# M865C.net
KiCad netlist of a schematic drawn in EAGLE
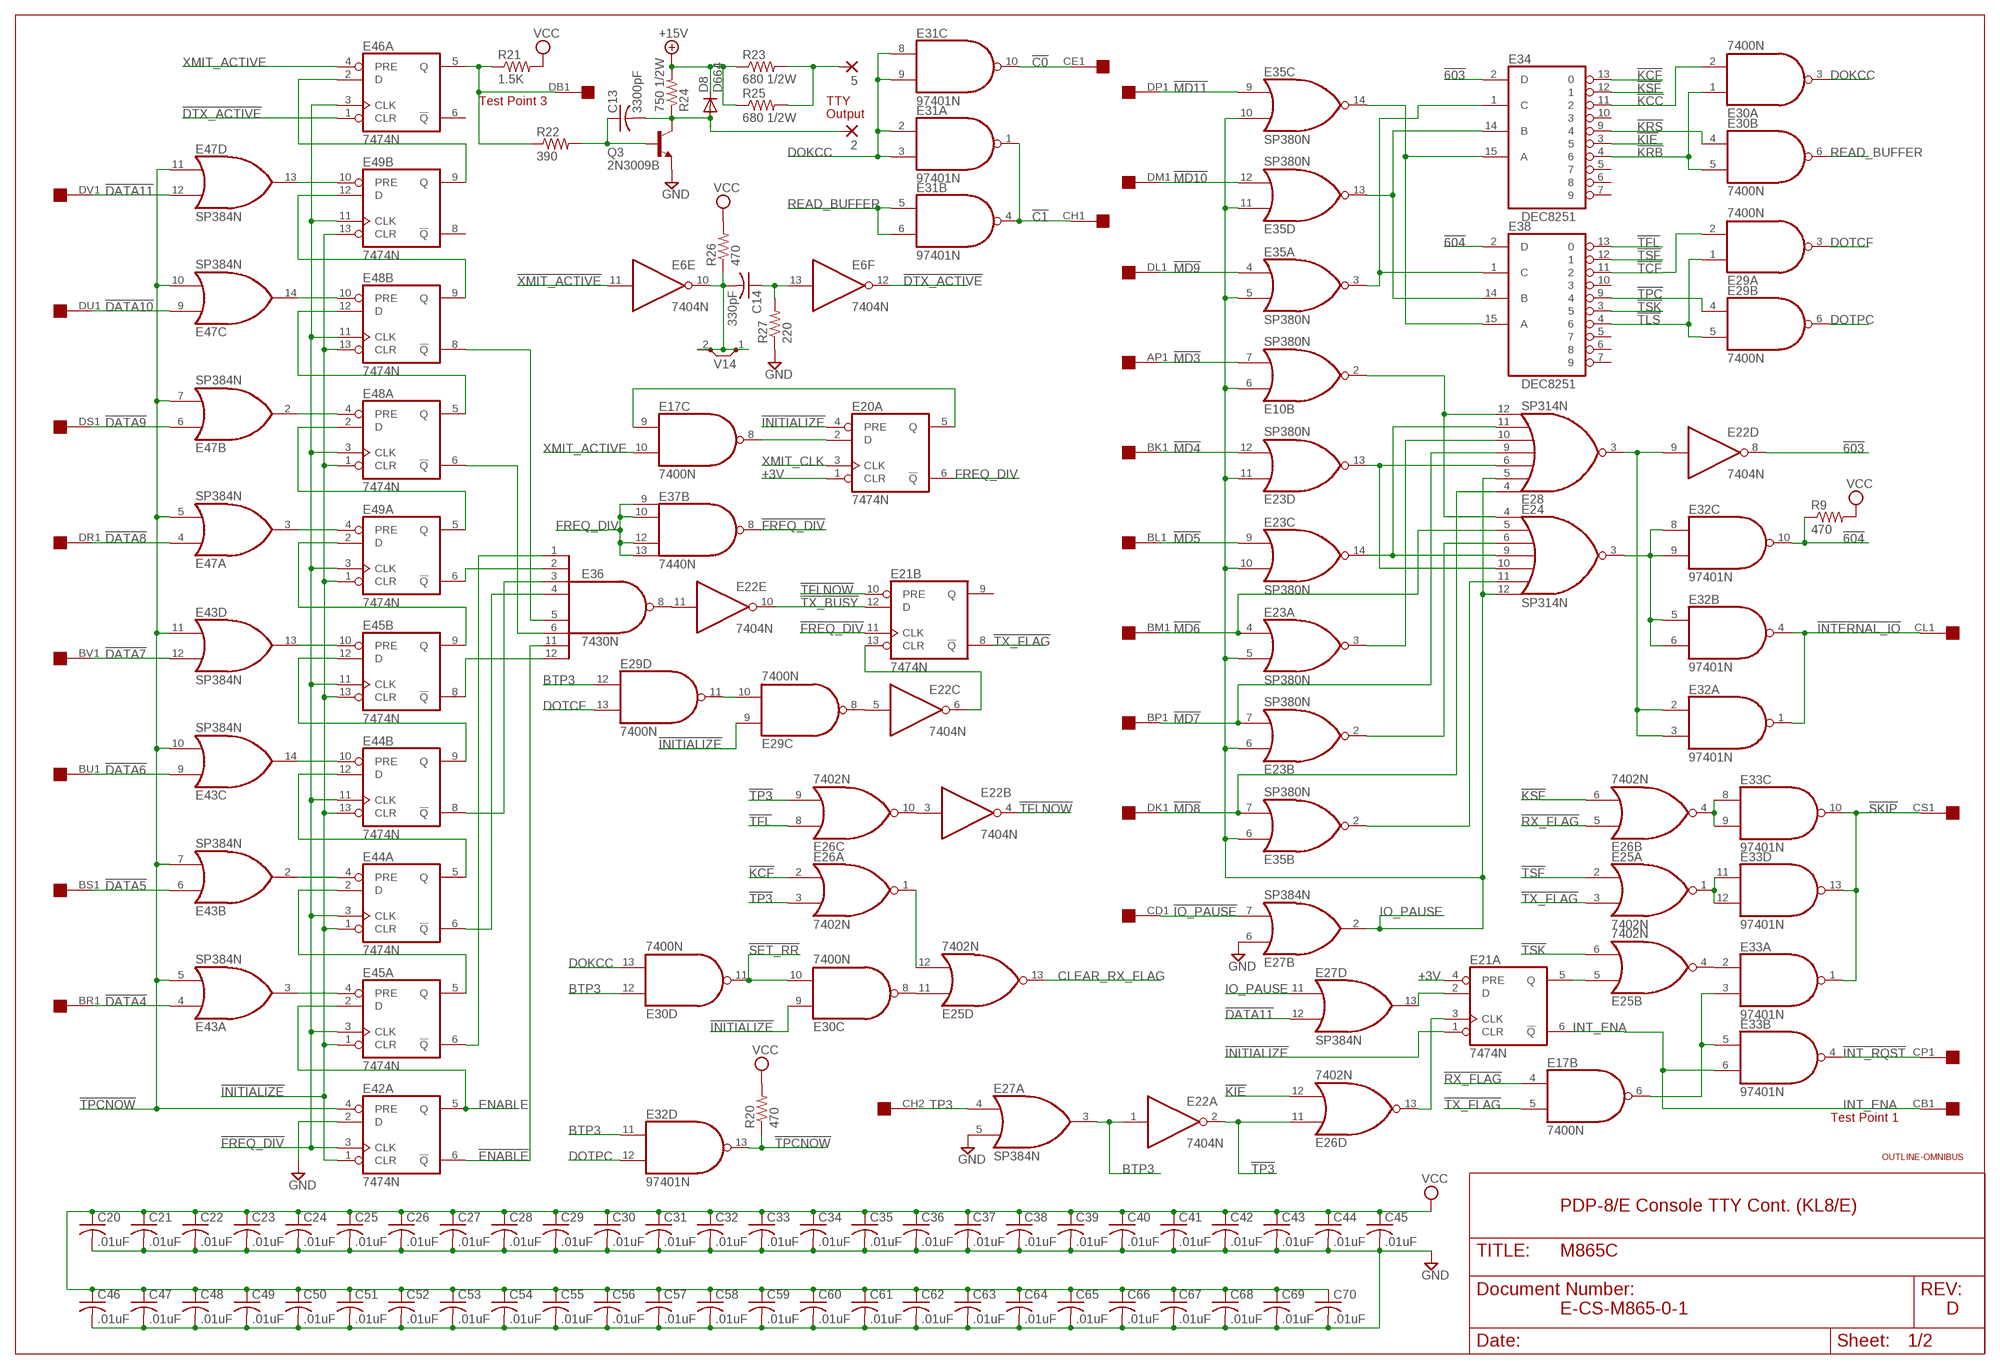
[diagram p0: schematic, sheet 1]
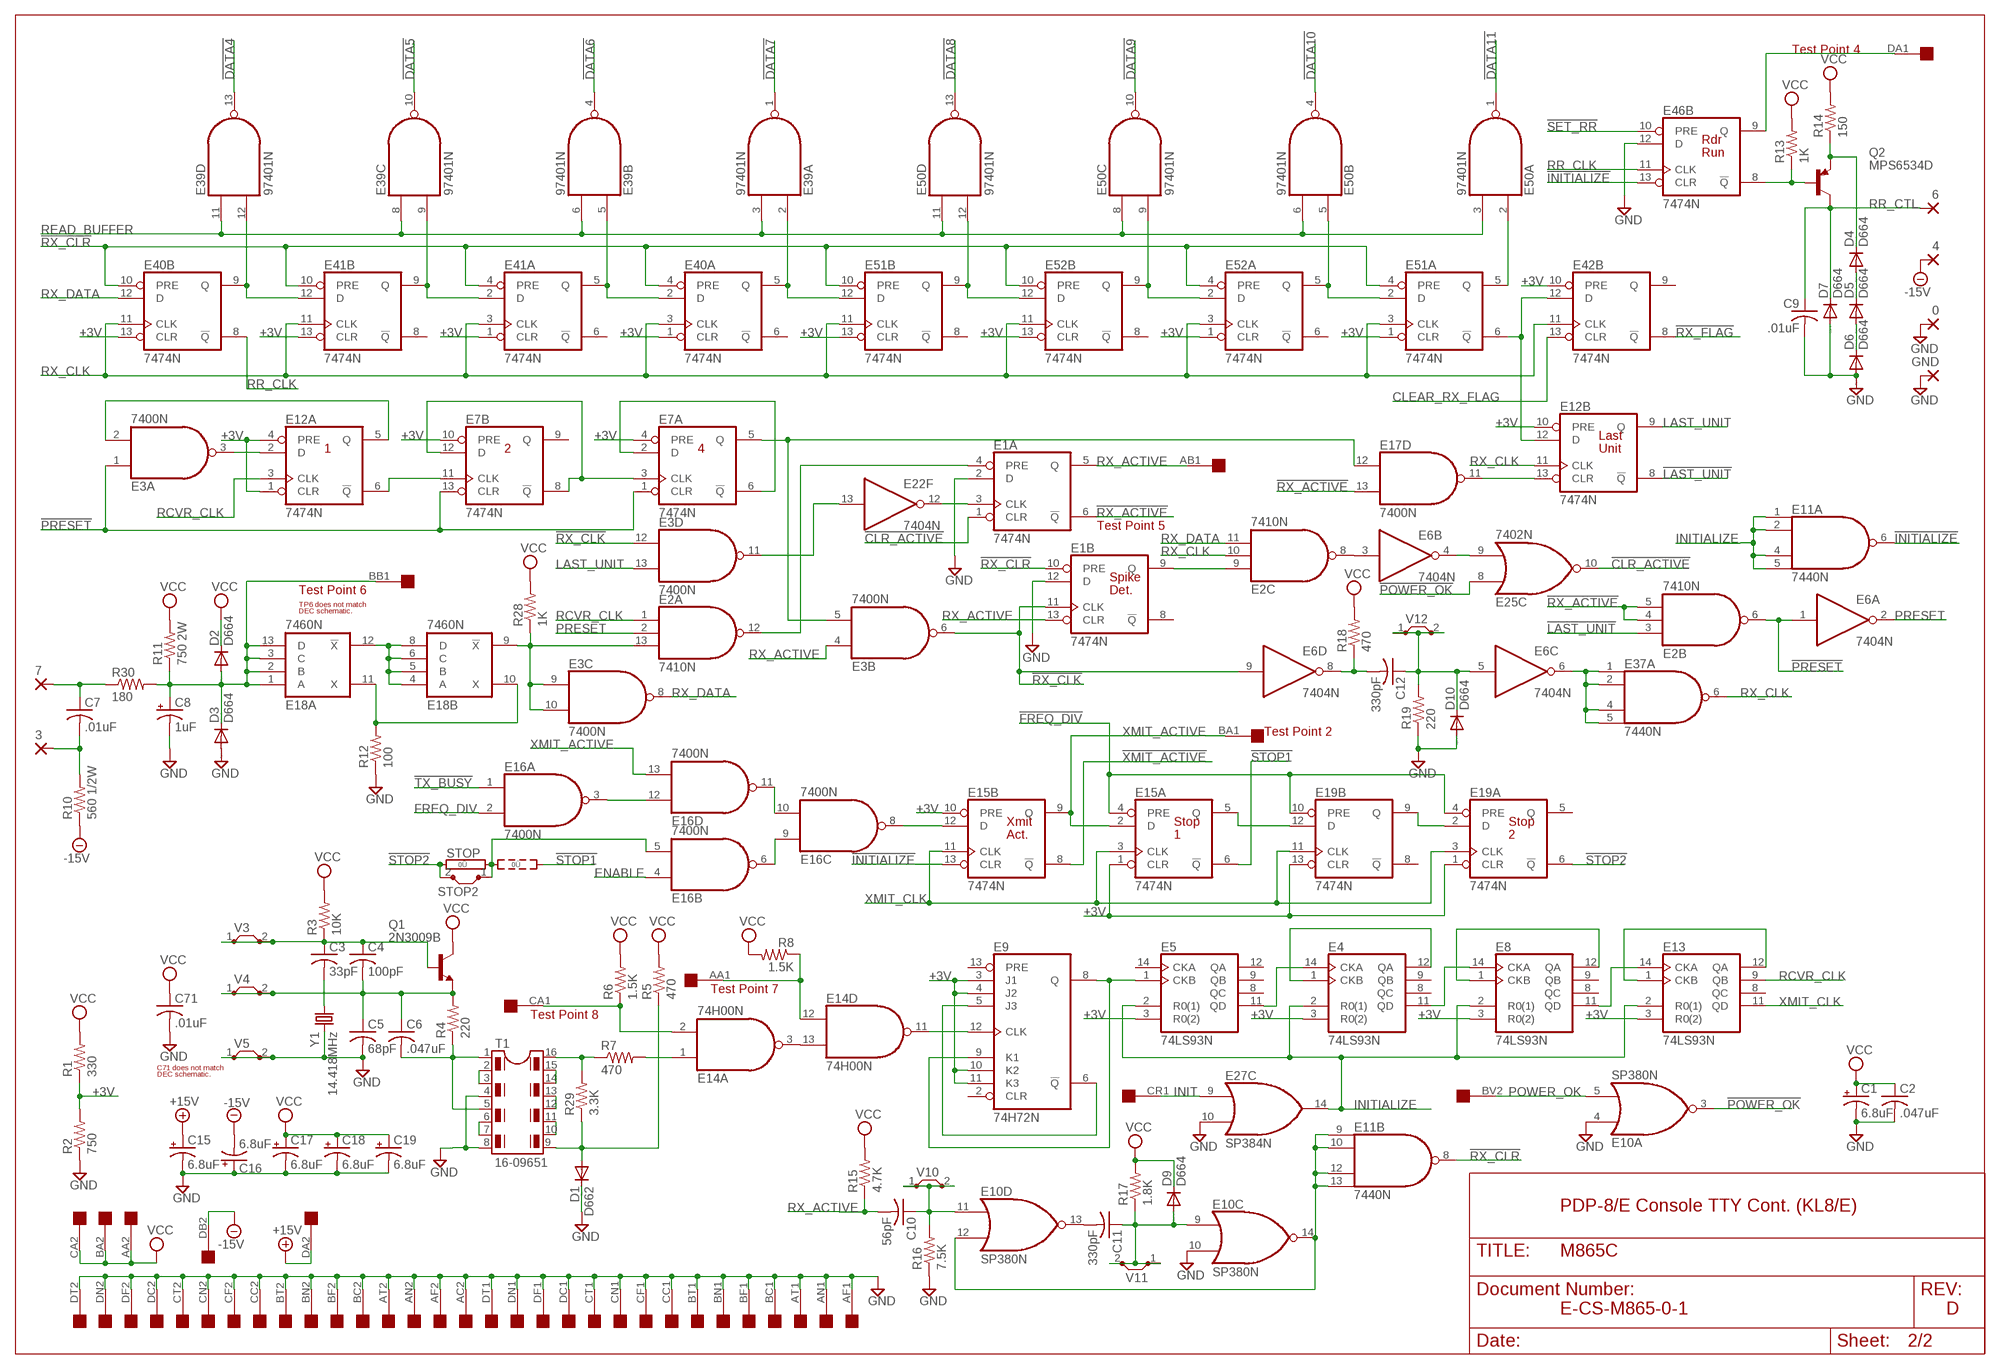
[diagram p1: schematic, sheet 2]

(export (version "E")
  (design (tool "Eeschema 10.0.6"))
  (components
    (comp (ref "0")
      (value "2,15/1,0")
      (footprint "eagle-import:2,15_1,0")
      (libsource (lib "eagle-import") (part "2,15/1,0"))
    )
    (comp (ref "3")
      (value "2,15/1,0")
      (footprint "eagle-import:2,15_1,0")
      (libsource (lib "eagle-import") (part "2,15/1,0"))
    )
    (comp (ref "4")
      (value "2,15/1,0")
      (footprint "eagle-import:2,15_1,0")
      (libsource (lib "eagle-import") (part "2,15/1,0"))
    )
    (comp (ref "6")
      (value "2,15/1,0")
      (footprint "eagle-import:2,15_1,0")
      (libsource (lib "eagle-import") (part "2,15/1,0"))
    )
    (comp (ref "7")
      (value "2,15/1,0")
      (footprint "eagle-import:2,15_1,0")
      (libsource (lib "eagle-import") (part "2,15/1,0"))
    )
    (comp (ref "C1")
      (value "6.8uF")
      (footprint "eagle-import:E12-8")
      (libsource (lib "eagle-import") (part "CPOL-USE20-8AXIAL"))
    )
    (comp (ref "C2")
      (value ".047uF")
      (footprint "eagle-import:C075-032X103")
      (libsource (lib "eagle-import") (part "C-US075-032X103"))
    )
    (comp (ref "C3")
      (value "33pF")
      (footprint "eagle-import:C050-025X075")
      (libsource (lib "eagle-import") (part "C-US050-025X075"))
    )
    (comp (ref "C4")
      (value "100pF")
      (footprint "eagle-import:C050-025X075")
      (libsource (lib "eagle-import") (part "C-US050-025X075"))
    )
    (comp (ref "C5")
      (value "68pF")
      (footprint "eagle-import:C050-025X075")
      (libsource (lib "eagle-import") (part "C-US050-025X075"))
    )
    (comp (ref "C6")
      (value ".047uF")
      (footprint "eagle-import:C075-032X103")
      (libsource (lib "eagle-import") (part "C-US075-032X103"))
    )
    (comp (ref "C7")
      (value ".01uF")
      (footprint "eagle-import:C050-025X075")
      (libsource (lib "eagle-import") (part "C-US050-025X075"))
    )
    (comp (ref "C8")
      (value "1uF")
      (footprint "eagle-import:E15-5")
      (libsource (lib "eagle-import") (part "CPOL-USE15-5AXIAL"))
    )
    (comp (ref "C9")
      (value ".01uF")
      (footprint "eagle-import:C050-025X075")
      (libsource (lib "eagle-import") (part "C-US050-025X075"))
    )
    (comp (ref "C10")
      (value "56pF")
      (footprint "eagle-import:C050-025X075")
      (libsource (lib "eagle-import") (part "C-US050-025X075"))
    )
    (comp (ref "C11")
      (value "330pF")
      (footprint "eagle-import:C050-025X075")
      (libsource (lib "eagle-import") (part "C-US050-025X075"))
    )
    (comp (ref "C12")
      (value "330pF")
      (footprint "eagle-import:C050-025X075")
      (libsource (lib "eagle-import") (part "C-US050-025X075"))
    )
    (comp (ref "C15")
      (value "6.8uF")
      (footprint "eagle-import:E12-8")
      (libsource (lib "eagle-import") (part "CPOL-USE20-8AXIAL"))
    )
    (comp (ref "C16")
      (value "6.8uF")
      (footprint "eagle-import:E12-8")
      (libsource (lib "eagle-import") (part "CPOL-USE20-8AXIAL"))
    )
    (comp (ref "C17")
      (value "6.8uF")
      (footprint "eagle-import:E12-8")
      (libsource (lib "eagle-import") (part "CPOL-USE20-8AXIAL"))
    )
    (comp (ref "C18")
      (value "6.8uF")
      (footprint "eagle-import:E12-8")
      (libsource (lib "eagle-import") (part "CPOL-USE20-8AXIAL"))
    )
    (comp (ref "C19")
      (value "6.8uF")
      (footprint "eagle-import:E12-8")
      (libsource (lib "eagle-import") (part "CPOL-USE20-8AXIAL"))
    )
    (comp (ref "C71")
      (value ".01uF")
      (footprint "eagle-import:C050-025X075")
      (libsource (lib "eagle-import") (part "C-US050-025X075"))
    )
    (comp (ref "D1")
      (value "D662")
      (footprint "eagle-import:DO35-10")
      (libsource (lib "eagle-import") (part "DIODE-DO35-10"))
    )
    (comp (ref "D2")
      (value "D664")
      (footprint "eagle-import:DO35-10")
      (libsource (lib "eagle-import") (part "DIODE-DO35-10"))
    )
    (comp (ref "D3")
      (value "D664")
      (footprint "eagle-import:DO35-10")
      (libsource (lib "eagle-import") (part "DIODE-DO35-10"))
    )
    (comp (ref "D4")
      (value "D664")
      (footprint "eagle-import:DO35-10")
      (libsource (lib "eagle-import") (part "DIODE-DO35-10"))
    )
    (comp (ref "D5")
      (value "D664")
      (footprint "eagle-import:DO35-10")
      (libsource (lib "eagle-import") (part "DIODE-DO35-10"))
    )
    (comp (ref "D6")
      (value "D664")
      (footprint "eagle-import:DO35-10")
      (libsource (lib "eagle-import") (part "DIODE-DO35-10"))
    )
    (comp (ref "D7")
      (value "D664")
      (footprint "eagle-import:DO35-10")
      (libsource (lib "eagle-import") (part "DIODE-DO35-10"))
    )
    (comp (ref "D9")
      (value "D664")
      (footprint "eagle-import:DO35-10")
      (libsource (lib "eagle-import") (part "DIODE-DO35-10"))
    )
    (comp (ref "D10")
      (value "D664")
      (footprint "eagle-import:DO35-10")
      (libsource (lib "eagle-import") (part "DIODE-DO35-10"))
    )
    (comp (ref "E1")
      (value "7474N")
      (footprint "eagle-import:DIL14")
      (libsource (lib "eagle-import") (part "7474NS"))
    )
    (comp (ref "E2")
      (value "7410N")
      (footprint "eagle-import:DIL14")
      (libsource (lib "eagle-import") (part "7410N"))
    )
    (comp (ref "E3")
      (value "7400N")
      (footprint "eagle-import:DIL14")
      (libsource (lib "eagle-import") (part "7400N"))
    )
    (comp (ref "E4")
      (value "74LS93N")
      (footprint "eagle-import:DIL14")
      (libsource (lib "eagle-import") (part "7493NLS"))
    )
    (comp (ref "E5")
      (value "74LS93N")
      (footprint "eagle-import:DIL14")
      (libsource (lib "eagle-import") (part "7493NLS"))
    )
    (comp (ref "E6")
      (value "7404N")
      (footprint "eagle-import:DIL14")
      (libsource (lib "eagle-import") (part "7404N"))
    )
    (comp (ref "E7")
      (value "7474N")
      (footprint "eagle-import:DIL14")
      (libsource (lib "eagle-import") (part "7474NS"))
    )
    (comp (ref "E8")
      (value "74LS93N")
      (footprint "eagle-import:DIL14")
      (libsource (lib "eagle-import") (part "7493NLS"))
    )
    (comp (ref "E9")
      (value "74H72N")
      (footprint "eagle-import:DIL14")
      (libsource (lib "eagle-import") (part "7472N"))
    )
    (comp (ref "E10")
      (value "SP380N")
      (footprint "eagle-import:DIL14")
      (libsource (lib "eagle-import") (part "SP380N"))
    )
    (comp (ref "E11")
      (value "7440N")
      (footprint "eagle-import:DIL14")
      (libsource (lib "eagle-import") (part "7440N"))
    )
    (comp (ref "E12")
      (value "7474N")
      (footprint "eagle-import:DIL14")
      (libsource (lib "eagle-import") (part "7474NS"))
    )
    (comp (ref "E13")
      (value "74LS93N")
      (footprint "eagle-import:DIL14")
      (libsource (lib "eagle-import") (part "7493NLS"))
    )
    (comp (ref "E14")
      (value "74H00N")
      (footprint "eagle-import:DIL14")
      (libsource (lib "eagle-import") (part "7400N"))
    )
    (comp (ref "E15")
      (value "7474N")
      (footprint "eagle-import:DIL14")
      (libsource (lib "eagle-import") (part "7474NS"))
    )
    (comp (ref "E16")
      (value "7400N")
      (footprint "eagle-import:DIL14")
      (libsource (lib "eagle-import") (part "7400N"))
    )
    (comp (ref "E17")
      (value "7400N")
      (footprint "eagle-import:DIL14")
      (libsource (lib "eagle-import") (part "7400N"))
    )
    (comp (ref "E18")
      (value "7460N")
      (footprint "eagle-import:DIL14")
      (libsource (lib "eagle-import") (part "7460N"))
    )
    (comp (ref "E19")
      (value "7474N")
      (footprint "eagle-import:DIL14")
      (libsource (lib "eagle-import") (part "7474NS"))
    )
    (comp (ref "E22")
      (value "7404N")
      (footprint "eagle-import:DIL14")
      (libsource (lib "eagle-import") (part "7404N"))
    )
    (comp (ref "E25")
      (value "7402N")
      (footprint "eagle-import:DIL14")
      (libsource (lib "eagle-import") (part "7402N"))
    )
    (comp (ref "E27")
      (value "SP384N")
      (footprint "eagle-import:DIL14")
      (libsource (lib "eagle-import") (part "SP384N"))
    )
    (comp (ref "E37")
      (value "7440N")
      (footprint "eagle-import:DIL14")
      (libsource (lib "eagle-import") (part "7440N"))
    )
    (comp (ref "E39")
      (value "97401N")
      (footprint "eagle-import:DIL14")
      (libsource (lib "eagle-import") (part "7401NLS"))
    )
    (comp (ref "E40")
      (value "7474N")
      (footprint "eagle-import:DIL14")
      (libsource (lib "eagle-import") (part "7474NS"))
    )
    (comp (ref "E41")
      (value "7474N")
      (footprint "eagle-import:DIL14")
      (libsource (lib "eagle-import") (part "7474NS"))
    )
    (comp (ref "E42")
      (value "7474N")
      (footprint "eagle-import:DIL14")
      (libsource (lib "eagle-import") (part "7474NS"))
    )
    (comp (ref "E46")
      (value "7474N")
      (footprint "eagle-import:DIL14")
      (libsource (lib "eagle-import") (part "7474NS"))
    )
    (comp (ref "E50")
      (value "97401N")
      (footprint "eagle-import:DIL14")
      (libsource (lib "eagle-import") (part "7401NLS"))
    )
    (comp (ref "E51")
      (value "7474N")
      (footprint "eagle-import:DIL14")
      (libsource (lib "eagle-import") (part "7474NS"))
    )
    (comp (ref "E52")
      (value "7474N")
      (footprint "eagle-import:DIL14")
      (libsource (lib "eagle-import") (part "7474NS"))
    )
    (comp (ref "GND")
      (value "2,15/1,0")
      (footprint "eagle-import:2,15_1,0")
      (libsource (lib "eagle-import") (part "2,15/1,0"))
    )
    (comp (ref "Q1")
      (value "2N3009B")
      (footprint "eagle-import:TO5")
      (libsource (lib "eagle-import") (part "-NPN-TO5"))
    )
    (comp (ref "Q2")
      (value "MPS6534D")
      (footprint "eagle-import:TO5")
      (libsource (lib "eagle-import") (part "-PNP-TO5"))
    )
    (comp (ref "R1")
      (value "330")
      (footprint "eagle-import:0207_10")
      (libsource (lib "eagle-import") (part "R-US_0207/10"))
    )
    (comp (ref "R2")
      (value "750")
      (footprint "eagle-import:0207_10")
      (libsource (lib "eagle-import") (part "R-US_0207/10"))
    )
    (comp (ref "R3")
      (value "10K")
      (footprint "eagle-import:0207_10")
      (libsource (lib "eagle-import") (part "R-US_0207/10"))
    )
    (comp (ref "R4")
      (value "220")
      (footprint "eagle-import:0207_10")
      (libsource (lib "eagle-import") (part "R-US_0207/10"))
    )
    (comp (ref "R5")
      (value "470")
      (footprint "eagle-import:0207_10")
      (libsource (lib "eagle-import") (part "R-US_0207/10"))
    )
    (comp (ref "R6")
      (value "1.5K")
      (footprint "eagle-import:0207_10")
      (libsource (lib "eagle-import") (part "R-US_0207/10"))
    )
    (comp (ref "R7")
      (value "470")
      (footprint "eagle-import:0207_10")
      (libsource (lib "eagle-import") (part "R-US_0207/10"))
    )
    (comp (ref "R8")
      (value "1.5K")
      (footprint "eagle-import:0207_10")
      (libsource (lib "eagle-import") (part "R-US_0207/10"))
    )
    (comp (ref "R10")
      (value "560 1/2W")
      (footprint "eagle-import:0411_15")
      (libsource (lib "eagle-import") (part "R-US_0411/15"))
    )
    (comp (ref "R11")
      (value "750 2W")
      (footprint "eagle-import:0818_25")
      (libsource (lib "eagle-import") (part "R-US_0818/25"))
    )
    (comp (ref "R12")
      (value "100")
      (footprint "eagle-import:0207_10")
      (libsource (lib "eagle-import") (part "R-US_0207/10"))
    )
    (comp (ref "R13")
      (value "1K")
      (footprint "eagle-import:0207_10")
      (libsource (lib "eagle-import") (part "R-US_0207/10"))
    )
    (comp (ref "R14")
      (value "150")
      (footprint "eagle-import:0207_10")
      (libsource (lib "eagle-import") (part "R-US_0207/10"))
    )
    (comp (ref "R15")
      (value "4.7K")
      (footprint "eagle-import:0207_10")
      (libsource (lib "eagle-import") (part "R-US_0207/10"))
    )
    (comp (ref "R16")
      (value "7.5K")
      (footprint "eagle-import:0207_10")
      (libsource (lib "eagle-import") (part "R-US_0207/10"))
    )
    (comp (ref "R17")
      (value "1.8K")
      (footprint "eagle-import:0207_10")
      (libsource (lib "eagle-import") (part "R-US_0207/10"))
    )
    (comp (ref "R18")
      (value "470")
      (footprint "eagle-import:0207_10")
      (libsource (lib "eagle-import") (part "R-US_0207/10"))
    )
    (comp (ref "R19")
      (value "220")
      (footprint "eagle-import:0207_10")
      (libsource (lib "eagle-import") (part "R-US_0207/10"))
    )
    (comp (ref "R28")
      (value "1K")
      (footprint "eagle-import:0207_10")
      (libsource (lib "eagle-import") (part "R-US_0207/10"))
    )
    (comp (ref "R29")
      (value "3.3K")
      (footprint "eagle-import:0207_10")
      (libsource (lib "eagle-import") (part "R-US_0207/10"))
    )
    (comp (ref "R30")
      (value "180")
      (footprint "eagle-import:0207_10")
      (libsource (lib "eagle-import") (part "R-US_0207/10"))
    )
    (comp (ref "STOP")
      (value "0R2")
      (footprint "eagle-import:0R2_10")
      (libsource (lib "eagle-import") (part "0R2"))
    )
    (comp (ref "STOP2")
      (value "J10MM")
      (footprint "eagle-import:10")
      (libsource (lib "eagle-import") (part "J10MM"))
    )
    (comp (ref "T1")
      (value "16-09651")
      (footprint "eagle-import:DIL16")
      (libsource (lib "eagle-import") (part "DIL16"))
    )
    (comp (ref "U$1")
      (value "QUAD")
      (footprint "eagle-import:EDGE-CON8")
      (libsource (lib "eagle-import") (part "QUAD"))
    )
    (comp (ref "V3")
      (value "J10MM")
      (footprint "eagle-import:10")
      (libsource (lib "eagle-import") (part "J10MM"))
    )
    (comp (ref "V4")
      (value "J10MM")
      (footprint "eagle-import:10")
      (libsource (lib "eagle-import") (part "J10MM"))
    )
    (comp (ref "V5")
      (value "J10MM")
      (footprint "eagle-import:10")
      (libsource (lib "eagle-import") (part "J10MM"))
    )
    (comp (ref "V10")
      (value "J10MM")
      (footprint "eagle-import:10")
      (libsource (lib "eagle-import") (part "J10MM"))
    )
    (comp (ref "V11")
      (value "J10MM")
      (footprint "eagle-import:10")
      (libsource (lib "eagle-import") (part "J10MM"))
    )
    (comp (ref "V12")
      (value "J10MM")
      (footprint "eagle-import:10")
      (libsource (lib "eagle-import") (part "J10MM"))
    )
    (comp (ref "Y1")
      (value "14.418MHz")
      (footprint "eagle-import:HC18U-H")
      (libsource (lib "eagle-import") (part "CRYSTALHC18U-H"))
    )
    (comp (ref "2")
      (value "2,15/1,0")
      (footprint "eagle-import:2,15_1,0")
      (libsource (lib "eagle-import") (part "2,15/1,0"))
    )
    (comp (ref "5")
      (value "2,15/1,0")
      (footprint "eagle-import:2,15_1,0")
      (libsource (lib "eagle-import") (part "2,15/1,0"))
    )
    (comp (ref "C13")
      (value "3300pF")
      (footprint "eagle-import:C102-043X133")
      (libsource (lib "eagle-import") (part "C-US102-043X133"))
    )
    (comp (ref "C14")
      (value "330pF")
      (footprint "eagle-import:C050-025X075")
      (libsource (lib "eagle-import") (part "C-US050-025X075"))
    )
    (comp (ref "C20")
      (value ".01uF")
      (footprint "eagle-import:C050-025X075")
      (libsource (lib "eagle-import") (part "C-US050-025X075"))
    )
    (comp (ref "C21")
      (value ".01uF")
      (footprint "eagle-import:C050-025X075")
      (libsource (lib "eagle-import") (part "C-US050-025X075"))
    )
    (comp (ref "C22")
      (value ".01uF")
      (footprint "eagle-import:C050-025X075")
      (libsource (lib "eagle-import") (part "C-US050-025X075"))
    )
    (comp (ref "C23")
      (value ".01uF")
      (footprint "eagle-import:C050-025X075")
      (libsource (lib "eagle-import") (part "C-US050-025X075"))
    )
    (comp (ref "C24")
      (value ".01uF")
      (footprint "eagle-import:C050-025X075")
      (libsource (lib "eagle-import") (part "C-US050-025X075"))
    )
    (comp (ref "C25")
      (value ".01uF")
      (footprint "eagle-import:C050-025X075")
      (libsource (lib "eagle-import") (part "C-US050-025X075"))
    )
    (comp (ref "C26")
      (value ".01uF")
      (footprint "eagle-import:C050-025X075")
      (libsource (lib "eagle-import") (part "C-US050-025X075"))
    )
    (comp (ref "C27")
      (value ".01uF")
      (footprint "eagle-import:C050-025X075")
      (libsource (lib "eagle-import") (part "C-US050-025X075"))
    )
    (comp (ref "C28")
      (value ".01uF")
      (footprint "eagle-import:C050-025X075")
      (libsource (lib "eagle-import") (part "C-US050-025X075"))
    )
    (comp (ref "C29")
      (value ".01uF")
      (footprint "eagle-import:C050-025X075")
      (libsource (lib "eagle-import") (part "C-US050-025X075"))
    )
    (comp (ref "C30")
      (value ".01uF")
      (footprint "eagle-import:C050-025X075")
      (libsource (lib "eagle-import") (part "C-US050-025X075"))
    )
    (comp (ref "C31")
      (value ".01uF")
      (footprint "eagle-import:C050-025X075")
      (libsource (lib "eagle-import") (part "C-US050-025X075"))
    )
    (comp (ref "C32")
      (value ".01uF")
      (footprint "eagle-import:C050-025X075")
      (libsource (lib "eagle-import") (part "C-US050-025X075"))
    )
    (comp (ref "C33")
      (value ".01uF")
      (footprint "eagle-import:C050-025X075")
      (libsource (lib "eagle-import") (part "C-US050-025X075"))
    )
    (comp (ref "C34")
      (value ".01uF")
      (footprint "eagle-import:C050-025X075")
      (libsource (lib "eagle-import") (part "C-US050-025X075"))
    )
    (comp (ref "C35")
      (value ".01uF")
      (footprint "eagle-import:C050-025X075")
      (libsource (lib "eagle-import") (part "C-US050-025X075"))
    )
    (comp (ref "C36")
      (value ".01uF")
      (footprint "eagle-import:C050-025X075")
      (libsource (lib "eagle-import") (part "C-US050-025X075"))
    )
    (comp (ref "C37")
      (value ".01uF")
      (footprint "eagle-import:C050-025X075")
      (libsource (lib "eagle-import") (part "C-US050-025X075"))
    )
    (comp (ref "C38")
      (value ".01uF")
      (footprint "eagle-import:C050-025X075")
      (libsource (lib "eagle-import") (part "C-US050-025X075"))
    )
    (comp (ref "C39")
      (value ".01uF")
      (footprint "eagle-import:C050-025X075")
      (libsource (lib "eagle-import") (part "C-US050-025X075"))
    )
    (comp (ref "C40")
      (value ".01uF")
      (footprint "eagle-import:C050-025X075")
      (libsource (lib "eagle-import") (part "C-US050-025X075"))
    )
    (comp (ref "C41")
      (value ".01uF")
      (footprint "eagle-import:C050-025X075")
      (libsource (lib "eagle-import") (part "C-US050-025X075"))
    )
    (comp (ref "C42")
      (value ".01uF")
      (footprint "eagle-import:C050-025X075")
      (libsource (lib "eagle-import") (part "C-US050-025X075"))
    )
    (comp (ref "C43")
      (value ".01uF")
      (footprint "eagle-import:C050-025X075")
      (libsource (lib "eagle-import") (part "C-US050-025X075"))
    )
    (comp (ref "C44")
      (value ".01uF")
      (footprint "eagle-import:C050-025X075")
      (libsource (lib "eagle-import") (part "C-US050-025X075"))
    )
    (comp (ref "C45")
      (value ".01uF")
      (footprint "eagle-import:C050-025X075")
      (libsource (lib "eagle-import") (part "C-US050-025X075"))
    )
    (comp (ref "C46")
      (value ".01uF")
      (footprint "eagle-import:C050-025X075")
      (libsource (lib "eagle-import") (part "C-US050-025X075"))
    )
    (comp (ref "C47")
      (value ".01uF")
      (footprint "eagle-import:C050-025X075")
      (libsource (lib "eagle-import") (part "C-US050-025X075"))
    )
    (comp (ref "C48")
      (value ".01uF")
      (footprint "eagle-import:C050-025X075")
      (libsource (lib "eagle-import") (part "C-US050-025X075"))
    )
    (comp (ref "C49")
      (value ".01uF")
      (footprint "eagle-import:C050-025X075")
      (libsource (lib "eagle-import") (part "C-US050-025X075"))
    )
    (comp (ref "C50")
      (value ".01uF")
      (footprint "eagle-import:C050-025X075")
      (libsource (lib "eagle-import") (part "C-US050-025X075"))
    )
    (comp (ref "C51")
      (value ".01uF")
      (footprint "eagle-import:C050-025X075")
      (libsource (lib "eagle-import") (part "C-US050-025X075"))
    )
    (comp (ref "C52")
      (value ".01uF")
      (footprint "eagle-import:C050-025X075")
      (libsource (lib "eagle-import") (part "C-US050-025X075"))
    )
    (comp (ref "C53")
      (value ".01uF")
      (footprint "eagle-import:C050-025X075")
      (libsource (lib "eagle-import") (part "C-US050-025X075"))
    )
    (comp (ref "C54")
      (value ".01uF")
      (footprint "eagle-import:C050-025X075")
      (libsource (lib "eagle-import") (part "C-US050-025X075"))
    )
    (comp (ref "C55")
      (value ".01uF")
      (footprint "eagle-import:C050-025X075")
      (libsource (lib "eagle-import") (part "C-US050-025X075"))
    )
    (comp (ref "C56")
      (value ".01uF")
      (footprint "eagle-import:C050-025X075")
      (libsource (lib "eagle-import") (part "C-US050-025X075"))
    )
    (comp (ref "C57")
      (value ".01uF")
      (footprint "eagle-import:C050-025X075")
      (libsource (lib "eagle-import") (part "C-US050-025X075"))
    )
    (comp (ref "C58")
      (value ".01uF")
      (footprint "eagle-import:C050-025X075")
      (libsource (lib "eagle-import") (part "C-US050-025X075"))
    )
    (comp (ref "C59")
      (value ".01uF")
      (footprint "eagle-import:C050-025X075")
      (libsource (lib "eagle-import") (part "C-US050-025X075"))
    )
    (comp (ref "C60")
      (value ".01uF")
      (footprint "eagle-import:C050-025X075")
      (libsource (lib "eagle-import") (part "C-US050-025X075"))
    )
    (comp (ref "C61")
      (value ".01uF")
      (footprint "eagle-import:C050-025X075")
      (libsource (lib "eagle-import") (part "C-US050-025X075"))
    )
    (comp (ref "C62")
      (value ".01uF")
      (footprint "eagle-import:C050-025X075")
      (libsource (lib "eagle-import") (part "C-US050-025X075"))
    )
    (comp (ref "C63")
      (value ".01uF")
      (footprint "eagle-import:C050-025X075")
      (libsource (lib "eagle-import") (part "C-US050-025X075"))
    )
    (comp (ref "C64")
      (value ".01uF")
      (footprint "eagle-import:C050-025X075")
      (libsource (lib "eagle-import") (part "C-US050-025X075"))
    )
    (comp (ref "C65")
      (value ".01uF")
      (footprint "eagle-import:C050-025X075")
      (libsource (lib "eagle-import") (part "C-US050-025X075"))
    )
    (comp (ref "C66")
      (value ".01uF")
      (footprint "eagle-import:C050-025X075")
      (libsource (lib "eagle-import") (part "C-US050-025X075"))
    )
    (comp (ref "C67")
      (value ".01uF")
      (footprint "eagle-import:C050-025X075")
      (libsource (lib "eagle-import") (part "C-US050-025X075"))
    )
    (comp (ref "C68")
      (value ".01uF")
      (footprint "eagle-import:C050-025X075")
      (libsource (lib "eagle-import") (part "C-US050-025X075"))
    )
    (comp (ref "C69")
      (value ".01uF")
      (footprint "eagle-import:C050-025X075")
      (libsource (lib "eagle-import") (part "C-US050-025X075"))
    )
    (comp (ref "C70")
      (value ".01uF")
      (footprint "eagle-import:C050-025X075")
      (libsource (lib "eagle-import") (part "C-US050-025X075"))
    )
    (comp (ref "D8")
      (value "D664")
      (footprint "eagle-import:DO35-10")
      (libsource (lib "eagle-import") (part "DIODE-DO35-10"))
    )
    (comp (ref "E20")
      (value "7474N")
      (footprint "eagle-import:DIL14")
      (libsource (lib "eagle-import") (part "7474NS"))
    )
    (comp (ref "E21")
      (value "7474N")
      (footprint "eagle-import:DIL14")
      (libsource (lib "eagle-import") (part "7474NS"))
    )
    (comp (ref "E23")
      (value "SP380N")
      (footprint "eagle-import:DIL14")
      (libsource (lib "eagle-import") (part "SP380N"))
    )
    (comp (ref "E24")
      (value "SP314N")
      (footprint "eagle-import:DIL14")
      (libsource (lib "eagle-import") (part "SP314N"))
    )
    (comp (ref "E26")
      (value "7402N")
      (footprint "eagle-import:DIL14")
      (libsource (lib "eagle-import") (part "7402N"))
    )
    (comp (ref "E28")
      (value "SP314N")
      (footprint "eagle-import:DIL14")
      (libsource (lib "eagle-import") (part "SP314N"))
    )
    (comp (ref "E29")
      (value "7400N")
      (footprint "eagle-import:DIL14")
      (libsource (lib "eagle-import") (part "7400N"))
    )
    (comp (ref "E30")
      (value "7400N")
      (footprint "eagle-import:DIL14")
      (libsource (lib "eagle-import") (part "7400N"))
    )
    (comp (ref "E31")
      (value "97401N")
      (footprint "eagle-import:DIL14")
      (libsource (lib "eagle-import") (part "7401NLS"))
    )
    (comp (ref "E32")
      (value "97401N")
      (footprint "eagle-import:DIL14")
      (libsource (lib "eagle-import") (part "7401NLS"))
    )
    (comp (ref "E33")
      (value "97401N")
      (footprint "eagle-import:DIL14")
      (libsource (lib "eagle-import") (part "7401NLS"))
    )
    (comp (ref "E34")
      (value "DEC8251")
      (footprint "eagle-import:DIL16")
      (libsource (lib "eagle-import") (part "DEC8251"))
    )
    (comp (ref "E35")
      (value "SP380N")
      (footprint "eagle-import:DIL14")
      (libsource (lib "eagle-import") (part "SP380N"))
    )
    (comp (ref "E36")
      (value "7430N")
      (footprint "eagle-import:DIL14")
      (libsource (lib "eagle-import") (part "7430N"))
    )
    (comp (ref "E38")
      (value "DEC8251")
      (footprint "eagle-import:DIL16")
      (libsource (lib "eagle-import") (part "DEC8251"))
    )
    (comp (ref "E43")
      (value "SP384N")
      (footprint "eagle-import:DIL14")
      (libsource (lib "eagle-import") (part "SP384N"))
    )
    (comp (ref "E44")
      (value "7474N")
      (footprint "eagle-import:DIL14")
      (libsource (lib "eagle-import") (part "7474NS"))
    )
    (comp (ref "E45")
      (value "7474N")
      (footprint "eagle-import:DIL14")
      (libsource (lib "eagle-import") (part "7474NS"))
    )
    (comp (ref "E47")
      (value "SP384N")
      (footprint "eagle-import:DIL14")
      (libsource (lib "eagle-import") (part "SP384N"))
    )
    (comp (ref "E48")
      (value "7474N")
      (footprint "eagle-import:DIL14")
      (libsource (lib "eagle-import") (part "7474NS"))
    )
    (comp (ref "E49")
      (value "7474N")
      (footprint "eagle-import:DIL14")
      (libsource (lib "eagle-import") (part "7474NS"))
    )
    (comp (ref "Q3")
      (value "2N3009B")
      (footprint "eagle-import:TO5")
      (libsource (lib "eagle-import") (part "-NPN-TO5"))
    )
    (comp (ref "R9")
      (value "470")
      (footprint "eagle-import:0207_10")
      (libsource (lib "eagle-import") (part "R-US_0207/10"))
    )
    (comp (ref "R20")
      (value "470")
      (footprint "eagle-import:0207_10")
      (libsource (lib "eagle-import") (part "R-US_0207/10"))
    )
    (comp (ref "R21")
      (value "1.5K")
      (footprint "eagle-import:0207_10")
      (libsource (lib "eagle-import") (part "R-US_0207/10"))
    )
    (comp (ref "R22")
      (value "390")
      (footprint "eagle-import:0207_10")
      (libsource (lib "eagle-import") (part "R-US_0207/10"))
    )
    (comp (ref "R23")
      (value "680 1/2W")
      (footprint "eagle-import:0411_15")
      (libsource (lib "eagle-import") (part "R-US_0411/15"))
    )
    (comp (ref "R24")
      (value "750 1/2W")
      (footprint "eagle-import:0411_15")
      (libsource (lib "eagle-import") (part "R-US_0411/15"))
    )
    (comp (ref "R25")
      (value "680 1/2W")
      (footprint "eagle-import:0411_15")
      (libsource (lib "eagle-import") (part "R-US_0411/15"))
    )
    (comp (ref "R26")
      (value "470")
      (footprint "eagle-import:0207_10")
      (libsource (lib "eagle-import") (part "R-US_0207/10"))
    )
    (comp (ref "R27")
      (value "220")
      (footprint "eagle-import:0207_10")
      (libsource (lib "eagle-import") (part "R-US_0207/10"))
    )
    (comp (ref "U$2")
      (value "OUTLINE-OMNIBUS")
      (footprint "eagle-import:OMNIBUS")
      (libsource (lib "eagle-import") (part "OUTLINE-OMNIBUS"))
    )
    (comp (ref "V14")
      (value "J10MM")
      (footprint "eagle-import:10")
      (libsource (lib "eagle-import") (part "J10MM"))
    )
  )
  (nets
    (net (code "1") (name "+3V") (class "Default")
      (node (ref "E12") (pin "1") (pinfunction "CLR_1") (pintype "input"))
      (node (ref "E12") (pin "10") (pinfunction "PRE_10") (pintype "input"))
      (node (ref "E12") (pin "4") (pinfunction "PRE_4") (pintype "input"))
      (node (ref "E13") (pin "3") (pinfunction "R0(2)_3") (pintype "input"))
      (node (ref "E15") (pin "1") (pinfunction "CLR_1") (pintype "input"))
      (node (ref "E15") (pin "10") (pinfunction "PRE_10") (pintype "input"))
      (node (ref "E19") (pin "1") (pinfunction "CLR_1") (pintype "input"))
      (node (ref "E19") (pin "13") (pinfunction "CLR_13") (pintype "input"))
      (node (ref "E20") (pin "1") (pinfunction "CLR_1") (pintype "input"))
      (node (ref "E21") (pin "4") (pinfunction "PRE_4") (pintype "input"))
      (node (ref "E4") (pin "3") (pinfunction "R0(2)_3") (pintype "input"))
      (node (ref "E40") (pin "1") (pinfunction "CLR_1") (pintype "input"))
      (node (ref "E40") (pin "13") (pinfunction "CLR_13") (pintype "input"))
      (node (ref "E41") (pin "1") (pinfunction "CLR_1") (pintype "input"))
      (node (ref "E41") (pin "13") (pinfunction "CLR_13") (pintype "input"))
      (node (ref "E42") (pin "10") (pinfunction "PRE_10") (pintype "input"))
      (node (ref "E5") (pin "3") (pinfunction "R0(2)_3") (pintype "input"))
      (node (ref "E51") (pin "1") (pinfunction "CLR_1") (pintype "input"))
      (node (ref "E51") (pin "13") (pinfunction "CLR_13") (pintype "input"))
      (node (ref "E52") (pin "1") (pinfunction "CLR_1") (pintype "input"))
      (node (ref "E52") (pin "13") (pinfunction "CLR_13") (pintype "input"))
      (node (ref "E7") (pin "10") (pinfunction "PRE_10") (pintype "input"))
      (node (ref "E7") (pin "4") (pinfunction "PRE_4") (pintype "input"))
      (node (ref "E8") (pin "3") (pinfunction "R0(2)_3") (pintype "input"))
      (node (ref "E9") (pin "10") (pinfunction "K2_10") (pintype "input"))
      (node (ref "E9") (pin "11") (pinfunction "K3_11") (pintype "input"))
      (node (ref "E9") (pin "3") (pinfunction "J1_3") (pintype "input"))
      (node (ref "E9") (pin "4") (pinfunction "J2_4") (pintype "input"))
      (node (ref "R1") (pin "1") (pinfunction "1_1") (pintype "passive"))
      (node (ref "R2") (pin "2") (pinfunction "2_2") (pintype "passive"))
    )
    (net (code "2") (name "+15V") (class "Default")
      (node (ref "C15") (pin "+") (pinfunction "+_+") (pintype "passive"))
      (node (ref "D8") (pin "C") (pinfunction "C_C") (pintype "passive"))
      (node (ref "R23") (pin "1") (pinfunction "1_1") (pintype "passive"))
      (node (ref "R24") (pin "2") (pinfunction "2_2") (pintype "passive"))
      (node (ref "R25") (pin "1") (pinfunction "1_1") (pintype "passive"))
      (node (ref "U$1") (pin "DA2") (pinfunction "1_DA2") (pintype "bidirectional"))
    )
    (net (code "3") (name "-15V") (class "Default")
      (node (ref "4") (pin "1") (pinfunction "P_1") (pintype "passive"))
      (node (ref "C16") (pin "-") (pinfunction "-_-") (pintype "passive"))
      (node (ref "R10") (pin "1") (pinfunction "1_1") (pintype "passive"))
      (node (ref "U$1") (pin "DB2") (pinfunction "1_DB2") (pintype "bidirectional"))
    )
    (net (code "4") (name "BTP3") (class "Default")
      (node (ref "E22") (pin "1") (pinfunction "I_1") (pintype "input"))
      (node (ref "E27") (pin "3") (pinfunction "O_3") (pintype "output"))
      (node (ref "E29") (pin "12") (pinfunction "I0_12") (pintype "input"))
      (node (ref "E30") (pin "12") (pinfunction "I0_12") (pintype "input"))
      (node (ref "E32") (pin "11") (pinfunction "I0_11") (pintype "input"))
    )
    (net (code "5") (name "CLEAR_RX_FLAG") (class "Default")
      (node (ref "E25") (pin "13") (pinfunction "O_13") (pintype "output"))
      (node (ref "E42") (pin "13") (pinfunction "CLR_13") (pintype "input"))
    )
    (net (code "6") (name "DOKCC") (class "Default")
      (node (ref "E30") (pin "13") (pinfunction "I1_13") (pintype "input"))
      (node (ref "E30") (pin "3") (pinfunction "O_3") (pintype "output"))
      (node (ref "E31") (pin "2") (pinfunction "I0_2") (pintype "input"))
      (node (ref "E31") (pin "3") (pinfunction "I1_3") (pintype "input"))
      (node (ref "E31") (pin "8") (pinfunction "I0_8") (pintype "input"))
      (node (ref "E31") (pin "9") (pinfunction "I1_9") (pintype "input"))
    )
    (net (code "7") (name "DOTCF") (class "Default")
      (node (ref "E29") (pin "13") (pinfunction "I1_13") (pintype "input"))
      (node (ref "E29") (pin "3") (pinfunction "O_3") (pintype "output"))
    )
    (net (code "8") (name "DOTPC") (class "Default")
      (node (ref "E29") (pin "6") (pinfunction "O_6") (pintype "output"))
      (node (ref "E32") (pin "12") (pinfunction "I1_12") (pintype "input"))
    )
    (net (code "9") (name "ENABLE") (class "Default")
      (node (ref "E16") (pin "4") (pinfunction "I0_4") (pintype "input"))
      (node (ref "E42") (pin "5") (pinfunction "Q_5") (pintype "output"))
      (node (ref "E45") (pin "2") (pinfunction "D_2") (pintype "input"))
    )
    (net (code "10") (name "FREQ_DIV") (class "Default")
      (node (ref "E16") (pin "2") (pinfunction "I1_2") (pintype "input"))
      (node (ref "E20") (pin "6") (pinfunction "~{Q}_6") (pintype "output"))
      (node (ref "E37") (pin "10") (pinfunction "I1_10") (pintype "input"))
      (node (ref "E37") (pin "12") (pinfunction "I2_12") (pintype "input"))
      (node (ref "E37") (pin "13") (pinfunction "I3_13") (pintype "input"))
      (node (ref "E37") (pin "9") (pinfunction "I0_9") (pintype "input"))
    )
    (net (code "11") (name "GND") (class "Default")
      (node (ref "0") (pin "1") (pinfunction "P_1") (pintype "passive"))
      (node (ref "C1") (pin "-") (pinfunction "-_-") (pintype "passive"))
      (node (ref "C15") (pin "-") (pinfunction "-_-") (pintype "passive"))
      (node (ref "C16") (pin "+") (pinfunction "+_+") (pintype "passive"))
      (node (ref "C17") (pin "-") (pinfunction "-_-") (pintype "passive"))
      (node (ref "C18") (pin "-") (pinfunction "-_-") (pintype "passive"))
      (node (ref "C19") (pin "-") (pinfunction "-_-") (pintype "passive"))
      (node (ref "C2") (pin "2") (pinfunction "2_2") (pintype "passive"))
      (node (ref "C20") (pin "2") (pinfunction "2_2") (pintype "passive"))
      (node (ref "C21") (pin "2") (pinfunction "2_2") (pintype "passive"))
      (node (ref "C22") (pin "2") (pinfunction "2_2") (pintype "passive"))
      (node (ref "C23") (pin "2") (pinfunction "2_2") (pintype "passive"))
      (node (ref "C24") (pin "2") (pinfunction "2_2") (pintype "passive"))
      (node (ref "C25") (pin "2") (pinfunction "2_2") (pintype "passive"))
      (node (ref "C26") (pin "2") (pinfunction "2_2") (pintype "passive"))
      (node (ref "C27") (pin "2") (pinfunction "2_2") (pintype "passive"))
      (node (ref "C28") (pin "2") (pinfunction "2_2") (pintype "passive"))
      (node (ref "C29") (pin "2") (pinfunction "2_2") (pintype "passive"))
      (node (ref "C30") (pin "2") (pinfunction "2_2") (pintype "passive"))
      (node (ref "C31") (pin "2") (pinfunction "2_2") (pintype "passive"))
      (node (ref "C32") (pin "2") (pinfunction "2_2") (pintype "passive"))
      (node (ref "C33") (pin "2") (pinfunction "2_2") (pintype "passive"))
      (node (ref "C34") (pin "2") (pinfunction "2_2") (pintype "passive"))
      (node (ref "C35") (pin "2") (pinfunction "2_2") (pintype "passive"))
      (node (ref "C36") (pin "2") (pinfunction "2_2") (pintype "passive"))
      (node (ref "C37") (pin "2") (pinfunction "2_2") (pintype "passive"))
      (node (ref "C38") (pin "2") (pinfunction "2_2") (pintype "passive"))
      (node (ref "C39") (pin "2") (pinfunction "2_2") (pintype "passive"))
      (node (ref "C40") (pin "2") (pinfunction "2_2") (pintype "passive"))
      (node (ref "C41") (pin "2") (pinfunction "2_2") (pintype "passive"))
      (node (ref "C42") (pin "2") (pinfunction "2_2") (pintype "passive"))
      (node (ref "C43") (pin "2") (pinfunction "2_2") (pintype "passive"))
      (node (ref "C44") (pin "2") (pinfunction "2_2") (pintype "passive"))
      (node (ref "C45") (pin "2") (pinfunction "2_2") (pintype "passive"))
      (node (ref "C46") (pin "2") (pinfunction "2_2") (pintype "passive"))
      (node (ref "C47") (pin "2") (pinfunction "2_2") (pintype "passive"))
      (node (ref "C48") (pin "2") (pinfunction "2_2") (pintype "passive"))
      (node (ref "C49") (pin "2") (pinfunction "2_2") (pintype "passive"))
      (node (ref "C5") (pin "2") (pinfunction "2_2") (pintype "passive"))
      (node (ref "C50") (pin "2") (pinfunction "2_2") (pintype "passive"))
      (node (ref "C51") (pin "2") (pinfunction "2_2") (pintype "passive"))
      (node (ref "C52") (pin "2") (pinfunction "2_2") (pintype "passive"))
      (node (ref "C53") (pin "2") (pinfunction "2_2") (pintype "passive"))
      (node (ref "C54") (pin "2") (pinfunction "2_2") (pintype "passive"))
      (node (ref "C55") (pin "2") (pinfunction "2_2") (pintype "passive"))
      (node (ref "C56") (pin "2") (pinfunction "2_2") (pintype "passive"))
      (node (ref "C57") (pin "2") (pinfunction "2_2") (pintype "passive"))
      (node (ref "C58") (pin "2") (pinfunction "2_2") (pintype "passive"))
      (node (ref "C59") (pin "2") (pinfunction "2_2") (pintype "passive"))
      (node (ref "C60") (pin "2") (pinfunction "2_2") (pintype "passive"))
      (node (ref "C61") (pin "2") (pinfunction "2_2") (pintype "passive"))
      (node (ref "C62") (pin "2") (pinfunction "2_2") (pintype "passive"))
      (node (ref "C63") (pin "2") (pinfunction "2_2") (pintype "passive"))
      (node (ref "C64") (pin "2") (pinfunction "2_2") (pintype "passive"))
      (node (ref "C65") (pin "2") (pinfunction "2_2") (pintype "passive"))
      (node (ref "C66") (pin "2") (pinfunction "2_2") (pintype "passive"))
      (node (ref "C67") (pin "2") (pinfunction "2_2") (pintype "passive"))
      (node (ref "C68") (pin "2") (pinfunction "2_2") (pintype "passive"))
      (node (ref "C69") (pin "2") (pinfunction "2_2") (pintype "passive"))
      (node (ref "C70") (pin "2") (pinfunction "2_2") (pintype "passive"))
      (node (ref "C71") (pin "2") (pinfunction "2_2") (pintype "passive"))
      (node (ref "C8") (pin "-") (pinfunction "-_-") (pintype "passive"))
      (node (ref "C9") (pin "2") (pinfunction "2_2") (pintype "passive"))
      (node (ref "D1") (pin "C") (pinfunction "C_C") (pintype "passive"))
      (node (ref "D10") (pin "A") (pinfunction "A_A") (pintype "passive"))
      (node (ref "D3") (pin "A") (pinfunction "A_A") (pintype "passive"))
      (node (ref "D6") (pin "A") (pinfunction "A_A") (pintype "passive"))
      (node (ref "D7") (pin "A") (pinfunction "A_A") (pintype "passive"))
      (node (ref "E1") (pin "12") (pinfunction "D_12") (pintype "input"))
      (node (ref "E1") (pin "2") (pinfunction "D_2") (pintype "input"))
      (node (ref "E10") (pin "10") (pinfunction "I1_10") (pintype "input"))
      (node (ref "E10") (pin "4") (pinfunction "I0_4") (pintype "input"))
      (node (ref "E27") (pin "10") (pinfunction "I1_10") (pintype "input"))
      (node (ref "E27") (pin "5") (pinfunction "I1_5") (pintype "input"))
      (node (ref "E27") (pin "6") (pinfunction "I0_6") (pintype "input"))
      (node (ref "E42") (pin "2") (pinfunction "D_2") (pintype "input"))
      (node (ref "E46") (pin "12") (pinfunction "D_12") (pintype "input"))
      (node (ref "GND") (pin "1") (pinfunction "P_1") (pintype "passive"))
      (node (ref "Q3") (pin "1") (pinfunction "E_1") (pintype "passive"))
      (node (ref "R12") (pin "1") (pinfunction "1_1") (pintype "passive"))
      (node (ref "R16") (pin "1") (pinfunction "1_1") (pintype "passive"))
      (node (ref "R19") (pin "1") (pinfunction "1_1") (pintype "passive"))
      (node (ref "R2") (pin "1") (pinfunction "1_1") (pintype "passive"))
      (node (ref "R27") (pin "1") (pinfunction "1_1") (pintype "passive"))
      (node (ref "T1") (pin "4") (pinfunction "4_4") (pintype "passive"))
      (node (ref "T1") (pin "8") (pinfunction "8_8") (pintype "passive"))
      (node (ref "U$1") (pin "AC2") (pinfunction "1_AC2") (pintype "bidirectional"))
      (node (ref "U$1") (pin "AF1") (pinfunction "1_AF1") (pintype "bidirectional"))
      (node (ref "U$1") (pin "AF2") (pinfunction "1_AF2") (pintype "bidirectional"))
      (node (ref "U$1") (pin "AN1") (pinfunction "1_AN1") (pintype "bidirectional"))
      (node (ref "U$1") (pin "AN2") (pinfunction "1_AN2") (pintype "bidirectional"))
      (node (ref "U$1") (pin "AT1") (pinfunction "1_AT1") (pintype "bidirectional"))
      (node (ref "U$1") (pin "AT2") (pinfunction "1_AT2") (pintype "bidirectional"))
      (node (ref "U$1") (pin "BC1") (pinfunction "1_BC1") (pintype "bidirectional"))
      (node (ref "U$1") (pin "BC2") (pinfunction "1_BC2") (pintype "bidirectional"))
      (node (ref "U$1") (pin "BF1") (pinfunction "1_BF1") (pintype "bidirectional"))
      (node (ref "U$1") (pin "BF2") (pinfunction "1_BF2") (pintype "bidirectional"))
      (node (ref "U$1") (pin "BN1") (pinfunction "1_BN1") (pintype "bidirectional"))
      (node (ref "U$1") (pin "BN2") (pinfunction "1_BN2") (pintype "bidirectional"))
      (node (ref "U$1") (pin "BT1") (pinfunction "1_BT1") (pintype "bidirectional"))
      (node (ref "U$1") (pin "BT2") (pinfunction "1_BT2") (pintype "bidirectional"))
      (node (ref "U$1") (pin "CC1") (pinfunction "1_CC1") (pintype "bidirectional"))
      (node (ref "U$1") (pin "CC2") (pinfunction "1_CC2") (pintype "bidirectional"))
      (node (ref "U$1") (pin "CF1") (pinfunction "1_CF1") (pintype "bidirectional"))
      (node (ref "U$1") (pin "CF2") (pinfunction "1_CF2") (pintype "bidirectional"))
      (node (ref "U$1") (pin "CN1") (pinfunction "1_CN1") (pintype "bidirectional"))
      (node (ref "U$1") (pin "CN2") (pinfunction "1_CN2") (pintype "bidirectional"))
      (node (ref "U$1") (pin "CT1") (pinfunction "1_CT1") (pintype "bidirectional"))
      (node (ref "U$1") (pin "CT2") (pinfunction "1_CT2") (pintype "bidirectional"))
      (node (ref "U$1") (pin "DC1") (pinfunction "1_DC1") (pintype "bidirectional"))
      (node (ref "U$1") (pin "DC2") (pinfunction "1_DC2") (pintype "bidirectional"))
      (node (ref "U$1") (pin "DF1") (pinfunction "1_DF1") (pintype "bidirectional"))
      (node (ref "U$1") (pin "DF2") (pinfunction "1_DF2") (pintype "bidirectional"))
      (node (ref "U$1") (pin "DN1") (pinfunction "1_DN1") (pintype "bidirectional"))
      (node (ref "U$1") (pin "DN2") (pinfunction "1_DN2") (pintype "bidirectional"))
      (node (ref "U$1") (pin "DT1") (pinfunction "1_DT1") (pintype "bidirectional"))
      (node (ref "U$1") (pin "DT2") (pinfunction "1_DT2") (pintype "bidirectional"))
      (node (ref "V5") (pin "1") (pinfunction "1_1") (pintype "passive"))
      (node (ref "V5") (pin "2") (pinfunction "2_2") (pintype "passive"))
      (node (ref "Y1") (pin "2") (pinfunction "2_2") (pintype "passive"))
    )
    (net (code "12") (name "INIT") (class "Default")
      (node (ref "E27") (pin "9") (pinfunction "I0_9") (pintype "input"))
      (node (ref "U$1") (pin "CR1") (pinfunction "1_CR1") (pintype "bidirectional"))
    )
    (net (code "13") (name "INITIALIZE") (class "Default")
      (node (ref "E11") (pin "1") (pinfunction "I0_1") (pintype "input"))
      (node (ref "E11") (pin "2") (pinfunction "I1_2") (pintype "input"))
      (node (ref "E11") (pin "4") (pinfunction "I2_4") (pintype "input"))
      (node (ref "E11") (pin "5") (pinfunction "I3_5") (pintype "input"))
      (node (ref "E13") (pin "2") (pinfunction "R0(1)_2") (pintype "input"))
      (node (ref "E27") (pin "14") (pinfunction "O_14") (pintype "output"))
      (node (ref "E4") (pin "2") (pinfunction "R0(1)_2") (pintype "input"))
      (node (ref "E5") (pin "2") (pinfunction "R0(1)_2") (pintype "input"))
      (node (ref "E8") (pin "2") (pinfunction "R0(1)_2") (pintype "input"))
    )
    (net (code "14") (name "INT_ENA") (class "Default")
      (node (ref "E21") (pin "6") (pinfunction "~{Q}_6") (pintype "output"))
      (node (ref "E33") (pin "6") (pinfunction "I1_6") (pintype "input"))
      (node (ref "U$1") (pin "CB1") (pinfunction "1_CB1") (pintype "bidirectional"))
    )
    (net (code "15") (name "IO_PAUSE") (class "Default")
      (node (ref "E10") (pin "6") (pinfunction "I0_6") (pintype "input"))
      (node (ref "E23") (pin "10") (pinfunction "I1_10") (pintype "input"))
      (node (ref "E23") (pin "11") (pinfunction "I0_11") (pintype "input"))
      (node (ref "E23") (pin "5") (pinfunction "I1_5") (pintype "input"))
      (node (ref "E23") (pin "6") (pinfunction "I0_6") (pintype "input"))
      (node (ref "E24") (pin "12") (pinfunction "I6_12") (pintype "input"))
      (node (ref "E27") (pin "11") (pinfunction "I0_11") (pintype "input"))
      (node (ref "E27") (pin "2") (pinfunction "O_2") (pintype "output"))
      (node (ref "E28") (pin "5") (pinfunction "I1_5") (pintype "input"))
      (node (ref "E35") (pin "10") (pinfunction "I1_10") (pintype "input"))
      (node (ref "E35") (pin "11") (pinfunction "I0_11") (pintype "input"))
      (node (ref "E35") (pin "5") (pinfunction "I1_5") (pintype "input"))
      (node (ref "E35") (pin "6") (pinfunction "I0_6") (pintype "input"))
    )
    (net (code "16") (name "LAST_UNIT") (class "Default")
      (node (ref "E12") (pin "9") (pinfunction "Q_9") (pintype "output"))
      (node (ref "E3") (pin "13") (pinfunction "I1_13") (pintype "input"))
    )
    (net (code "17") (name "Net-(2-P)") (class "Default")
      (node (ref "2") (pin "1") (pinfunction "P_1") (pintype "passive"))
      (node (ref "C13") (pin "2") (pinfunction "2_2") (pintype "passive"))
      (node (ref "D8") (pin "A") (pinfunction "A_A") (pintype "passive"))
      (node (ref "Q3") (pin "3") (pinfunction "C_3") (pintype "passive"))
      (node (ref "R24") (pin "1") (pinfunction "1_1") (pintype "passive"))
    )
    (net (code "18") (name "Net-(3-P)") (class "Default")
      (node (ref "3") (pin "1") (pinfunction "P_1") (pintype "passive"))
      (node (ref "C7") (pin "2") (pinfunction "2_2") (pintype "passive"))
      (node (ref "R10") (pin "2") (pinfunction "2_2") (pintype "passive"))
    )
    (net (code "19") (name "Net-(5-P)") (class "Default")
      (node (ref "5") (pin "1") (pinfunction "P_1") (pintype "passive"))
      (node (ref "R23") (pin "2") (pinfunction "2_2") (pintype "passive"))
      (node (ref "R25") (pin "2") (pinfunction "2_2") (pintype "passive"))
    )
    (net (code "20") (name "Net-(7-P)") (class "Default")
      (node (ref "7") (pin "1") (pinfunction "P_1") (pintype "passive"))
      (node (ref "C7") (pin "1") (pinfunction "1_1") (pintype "passive"))
      (node (ref "R30") (pin "1") (pinfunction "1_1") (pintype "passive"))
    )
    (net (code "21") (name "Net-(C3-Pad2)") (class "Default")
      (node (ref "C3") (pin "2") (pinfunction "2_2") (pintype "passive"))
      (node (ref "Y1") (pin "1") (pinfunction "1_1") (pintype "passive"))
    )
    (net (code "22") (name "Net-(C6-Pad2)") (class "Default")
      (node (ref "C6") (pin "2") (pinfunction "2_2") (pintype "passive"))
      (node (ref "R4") (pin "1") (pinfunction "1_1") (pintype "passive"))
      (node (ref "T1") (pin "1") (pinfunction "1_1") (pintype "passive"))
      (node (ref "T1") (pin "5") (pinfunction "5_5") (pintype "passive"))
    )
    (net (code "23") (name "Net-(D1-PadA)") (class "Default")
      (node (ref "D1") (pin "A") (pinfunction "A_A") (pintype "passive"))
      (node (ref "R29") (pin "1") (pinfunction "1_1") (pintype "passive"))
      (node (ref "R5") (pin "1") (pinfunction "1_1") (pintype "passive"))
      (node (ref "T1") (pin "9") (pinfunction "9_9") (pintype "passive"))
    )
    (net (code "24") (name "Net-(D4-PadA)") (class "Default")
      (node (ref "D4") (pin "A") (pinfunction "A_A") (pintype "passive"))
      (node (ref "D5") (pin "C") (pinfunction "C_C") (pintype "passive"))
    )
    (net (code "25") (name "Net-(D5-PadA)") (class "Default")
      (node (ref "D5") (pin "A") (pinfunction "A_A") (pintype "passive"))
      (node (ref "D6") (pin "C") (pinfunction "C_C") (pintype "passive"))
    )
    (net (code "26") (name "Net-(E1A-CLK)") (class "Default")
      (node (ref "E1") (pin "3") (pinfunction "CLK_3") (pintype "input"))
      (node (ref "E22") (pin "12") (pinfunction "O_12") (pintype "output"))
    )
    (net (code "27") (name "Net-(E1A-PRE)") (class "Default")
      (node (ref "E1") (pin "4") (pinfunction "PRE_4") (pintype "input"))
      (node (ref "E2") (pin "12") (pinfunction "O_12") (pintype "output"))
    )
    (net (code "28") (name "Net-(E1B-Q)") (class "Default")
      (node (ref "E1") (pin "9") (pinfunction "Q_9") (pintype "output"))
      (node (ref "E2") (pin "9") (pinfunction "I0_9") (pintype "input"))
    )
    (net (code "29") (name "Net-(E2C-O)") (class "Default")
      (node (ref "E2") (pin "8") (pinfunction "O_8") (pintype "output"))
      (node (ref "E6") (pin "3") (pinfunction "I_3") (pintype "input"))
    )
    (net (code "30") (name "Net-(E4A-CKA)") (class "Default")
      (node (ref "E4") (pin "14") (pinfunction "CKA_14") (pintype "input"))
      (node (ref "E5") (pin "11") (pinfunction "QD_11") (pintype "output"))
    )
    (net (code "31") (name "Net-(E4A-CKB)") (class "Default")
      (node (ref "E4") (pin "1") (pinfunction "CKB_1") (pintype "input"))
      (node (ref "E4") (pin "12") (pinfunction "QA_12") (pintype "output"))
    )
    (net (code "32") (name "Net-(E4A-QD)") (class "Default")
      (node (ref "E4") (pin "11") (pinfunction "QD_11") (pintype "output"))
      (node (ref "E8") (pin "14") (pinfunction "CKA_14") (pintype "input"))
    )
    (net (code "33") (name "Net-(E5A-CKB)") (class "Default")
      (node (ref "E5") (pin "1") (pinfunction "CKB_1") (pintype "input"))
      (node (ref "E9") (pin "8") (pinfunction "Q_8") (pintype "output"))
      (node (ref "E9") (pin "9") (pinfunction "K1_9") (pintype "input"))
    )
    (net (code "34") (name "Net-(E6C-I)") (class "Default")
      (node (ref "C12") (pin "1") (pinfunction "1_1") (pintype "passive"))
      (node (ref "D10") (pin "C") (pinfunction "C_C") (pintype "passive"))
      (node (ref "E6") (pin "5") (pinfunction "I_5") (pintype "input"))
      (node (ref "R19") (pin "2") (pinfunction "2_2") (pintype "passive"))
      (node (ref "V12") (pin "1") (pinfunction "1_1") (pintype "passive"))
      (node (ref "V12") (pin "2") (pinfunction "2_2") (pintype "passive"))
    )
    (net (code "35") (name "Net-(E6D-O)") (class "Default")
      (node (ref "C12") (pin "2") (pinfunction "2_2") (pintype "passive"))
      (node (ref "E6") (pin "8") (pinfunction "O_8") (pintype "output"))
      (node (ref "R18") (pin "1") (pinfunction "1_1") (pintype "passive"))
    )
    (net (code "36") (name "Net-(E6E-O)") (class "Default")
      (node (ref "C14") (pin "2") (pinfunction "2_2") (pintype "passive"))
      (node (ref "E6") (pin "10") (pinfunction "O_10") (pintype "output"))
      (node (ref "R26") (pin "1") (pinfunction "1_1") (pintype "passive"))
      (node (ref "V14") (pin "1") (pinfunction "1_1") (pintype "passive"))
      (node (ref "V14") (pin "2") (pinfunction "2_2") (pintype "passive"))
    )
    (net (code "37") (name "Net-(E6F-I)") (class "Default")
      (node (ref "C14") (pin "1") (pinfunction "1_1") (pintype "passive"))
      (node (ref "E6") (pin "13") (pinfunction "I_13") (pintype "input"))
      (node (ref "R27") (pin "2") (pinfunction "2_2") (pintype "passive"))
    )
    (net (code "38") (name "Net-(E7A-CLK)") (class "Default")
      (node (ref "E7") (pin "12") (pinfunction "D_12") (pintype "input"))
      (node (ref "E7") (pin "3") (pinfunction "CLK_3") (pintype "input"))
      (node (ref "E7") (pin "8") (pinfunction "~{Q}_8") (pintype "output"))
    )
    (net (code "39") (name "Net-(E7A-D)") (class "Default")
      (node (ref "E7") (pin "2") (pinfunction "D_2") (pintype "input"))
      (node (ref "E7") (pin "6") (pinfunction "~{Q}_6") (pintype "output"))
    )
    (net (code "40") (name "Net-(E8A-CKB)") (class "Default")
      (node (ref "E8") (pin "1") (pinfunction "CKB_1") (pintype "input"))
      (node (ref "E8") (pin "12") (pinfunction "QA_12") (pintype "output"))
    )
    (net (code "41") (name "Net-(E9A-J3)") (class "Default")
      (node (ref "E9") (pin "5") (pinfunction "J3_5") (pintype "input"))
      (node (ref "E9") (pin "6") (pinfunction "~{Q}_6") (pintype "output"))
    )
    (net (code "42") (name "Net-(E10B-O)") (class "Default")
      (node (ref "E10") (pin "2") (pinfunction "O_2") (pintype "output"))
      (node (ref "E24") (pin "4") (pinfunction "I0_4") (pintype "input"))
      (node (ref "E28") (pin "12") (pinfunction "I6_12") (pintype "input"))
    )
    (net (code "43") (name "Net-(E10C-I0)") (class "Default")
      (node (ref "C11") (pin "1") (pinfunction "1_1") (pintype "passive"))
      (node (ref "D9") (pin "A") (pinfunction "A_A") (pintype "passive"))
      (node (ref "E10") (pin "9") (pinfunction "I0_9") (pintype "input"))
      (node (ref "R17") (pin "1") (pinfunction "1_1") (pintype "passive"))
      (node (ref "V11") (pin "1") (pinfunction "1_1") (pintype "passive"))
      (node (ref "V11") (pin "2") (pinfunction "2_2") (pintype "passive"))
    )
    (net (code "44") (name "Net-(E10C-O)") (class "Default")
      (node (ref "E10") (pin "12") (pinfunction "I1_12") (pintype "input"))
      (node (ref "E10") (pin "14") (pinfunction "O_14") (pintype "output"))
      (node (ref "E11") (pin "10") (pinfunction "I1_10") (pintype "input"))
      (node (ref "E11") (pin "12") (pinfunction "I2_12") (pintype "input"))
      (node (ref "E11") (pin "13") (pinfunction "I3_13") (pintype "input"))
      (node (ref "E11") (pin "9") (pinfunction "I0_9") (pintype "input"))
    )
    (net (code "45") (name "Net-(E10D-I0)") (class "Default")
      (node (ref "C10") (pin "1") (pinfunction "1_1") (pintype "passive"))
      (node (ref "E10") (pin "11") (pinfunction "I0_11") (pintype "input"))
      (node (ref "R16") (pin "2") (pinfunction "2_2") (pintype "passive"))
      (node (ref "V10") (pin "1") (pinfunction "1_1") (pintype "passive"))
      (node (ref "V10") (pin "2") (pinfunction "2_2") (pintype "passive"))
    )
    (net (code "46") (name "Net-(E10D-O)") (class "Default")
      (node (ref "C11") (pin "2") (pinfunction "2_2") (pintype "passive"))
      (node (ref "E10") (pin "13") (pinfunction "O_13") (pintype "output"))
    )
    (net (code "47") (name "Net-(E12A-D)") (class "Default")
      (node (ref "E12") (pin "2") (pinfunction "D_2") (pintype "input"))
      (node (ref "E3") (pin "3") (pinfunction "O_3") (pintype "output"))
    )
    (net (code "48") (name "Net-(E12A-Q)") (class "Default")
      (node (ref "E12") (pin "5") (pinfunction "Q_5") (pintype "output"))
      (node (ref "E3") (pin "2") (pinfunction "I1_2") (pintype "input"))
    )
    (net (code "49") (name "Net-(E12A-~{Q})") (class "Default")
      (node (ref "E12") (pin "6") (pinfunction "~{Q}_6") (pintype "output"))
      (node (ref "E7") (pin "11") (pinfunction "CLK_11") (pintype "input"))
    )
    (net (code "50") (name "Net-(E12B-CLR)") (class "Default")
      (node (ref "E12") (pin "13") (pinfunction "CLR_13") (pintype "input"))
      (node (ref "E17") (pin "11") (pinfunction "O_11") (pintype "output"))
    )
    (net (code "51") (name "Net-(E12B-D)") (class "Default")
      (node (ref "E12") (pin "12") (pinfunction "D_12") (pintype "input"))
      (node (ref "E42") (pin "12") (pinfunction "D_12") (pintype "input"))
      (node (ref "E51") (pin "6") (pinfunction "~{Q}_6") (pintype "output"))
    )
    (net (code "52") (name "Net-(E13A-CKA)") (class "Default")
      (node (ref "E13") (pin "14") (pinfunction "CKA_14") (pintype "input"))
      (node (ref "E8") (pin "11") (pinfunction "QD_11") (pintype "output"))
    )
    (net (code "53") (name "Net-(E13A-CKB)") (class "Default")
      (node (ref "E13") (pin "1") (pinfunction "CKB_1") (pintype "input"))
      (node (ref "E13") (pin "12") (pinfunction "QA_12") (pintype "output"))
    )
    (net (code "54") (name "Net-(E14A-I0)") (class "Default")
      (node (ref "E14") (pin "1") (pinfunction "I0_1") (pintype "input"))
      (node (ref "R7") (pin "2") (pinfunction "2_2") (pintype "passive"))
    )
    (net (code "55") (name "Net-(E14A-I1)") (class "Default")
      (node (ref "E14") (pin "2") (pinfunction "I1_2") (pintype "input"))
      (node (ref "R6") (pin "1") (pinfunction "1_1") (pintype "passive"))
      (node (ref "U$1") (pin "CA1") (pinfunction "1_CA1") (pintype "bidirectional"))
    )
    (net (code "56") (name "Net-(E14A-O)") (class "Default")
      (node (ref "E14") (pin "13") (pinfunction "I1_13") (pintype "input"))
      (node (ref "E14") (pin "3") (pinfunction "O_3") (pintype "output"))
    )
    (net (code "57") (name "Net-(E14D-I0)") (class "Default")
      (node (ref "E14") (pin "12") (pinfunction "I0_12") (pintype "input"))
      (node (ref "R8") (pin "1") (pinfunction "1_1") (pintype "passive"))
      (node (ref "U$1") (pin "AA1") (pinfunction "1_AA1") (pintype "bidirectional"))
    )
    (net (code "58") (name "Net-(E14D-O)") (class "Default")
      (node (ref "E14") (pin "11") (pinfunction "O_11") (pintype "output"))
      (node (ref "E9") (pin "12") (pinfunction "CLK_12") (pintype "input"))
    )
    (net (code "59") (name "Net-(E15A-Q)") (class "Default")
      (node (ref "E15") (pin "5") (pinfunction "Q_5") (pintype "output"))
      (node (ref "E19") (pin "12") (pinfunction "D_12") (pintype "input"))
    )
    (net (code "60") (name "Net-(E15B-D)") (class "Default")
      (node (ref "E15") (pin "12") (pinfunction "D_12") (pintype "input"))
      (node (ref "E16") (pin "8") (pinfunction "O_8") (pintype "output"))
    )
    (net (code "61") (name "Net-(E16A-O)") (class "Default")
      (node (ref "E16") (pin "12") (pinfunction "I0_12") (pintype "input"))
      (node (ref "E16") (pin "3") (pinfunction "O_3") (pintype "output"))
    )
    (net (code "62") (name "Net-(E16B-I1)") (class "Default")
      (node (ref "E16") (pin "5") (pinfunction "I1_5") (pintype "input"))
      (node (ref "STOP") (pin "2") (pinfunction "2_2") (pintype "passive"))
      (node (ref "STOP2") (pin "1") (pinfunction "1_1") (pintype "passive"))
    )
    (net (code "63") (name "Net-(E16B-O)") (class "Default")
      (node (ref "E16") (pin "6") (pinfunction "O_6") (pintype "output"))
      (node (ref "E16") (pin "9") (pinfunction "I0_9") (pintype "input"))
    )
    (net (code "64") (name "Net-(E16C-I1)") (class "Default")
      (node (ref "E16") (pin "10") (pinfunction "I1_10") (pintype "input"))
      (node (ref "E16") (pin "11") (pinfunction "O_11") (pintype "output"))
    )
    (net (code "65") (name "Net-(E17B-O)") (class "Default")
      (node (ref "E17") (pin "6") (pinfunction "O_6") (pintype "output"))
      (node (ref "E33") (pin "3") (pinfunction "I1_3") (pintype "input"))
      (node (ref "E33") (pin "5") (pinfunction "I0_5") (pintype "input"))
    )
    (net (code "66") (name "Net-(E17C-I0)") (class "Default")
      (node (ref "E17") (pin "9") (pinfunction "I0_9") (pintype "input"))
      (node (ref "E20") (pin "5") (pinfunction "Q_5") (pintype "output"))
    )
    (net (code "67") (name "Net-(E17C-O)") (class "Default")
      (node (ref "E17") (pin "8") (pinfunction "O_8") (pintype "output"))
      (node (ref "E20") (pin "2") (pinfunction "D_2") (pintype "input"))
    )
    (net (code "68") (name "Net-(E17D-I0)") (class "Default")
      (node (ref "E17") (pin "12") (pinfunction "I0_12") (pintype "input"))
      (node (ref "E3") (pin "5") (pinfunction "I1_5") (pintype "input"))
      (node (ref "E7") (pin "5") (pinfunction "Q_5") (pintype "output"))
    )
    (net (code "69") (name "Net-(E18A-A)") (class "Default")
      (node (ref "C8") (pin "+") (pinfunction "+_+") (pintype "passive"))
      (node (ref "D2") (pin "A") (pinfunction "A_A") (pintype "passive"))
      (node (ref "D3") (pin "C") (pinfunction "C_C") (pintype "passive"))
      (node (ref "E18") (pin "1") (pinfunction "A_1") (pintype "input"))
      (node (ref "E18") (pin "13") (pinfunction "D_13") (pintype "input"))
      (node (ref "E18") (pin "2") (pinfunction "B_2") (pintype "input"))
      (node (ref "E18") (pin "3") (pinfunction "C_3") (pintype "input"))
      (node (ref "R11") (pin "1") (pinfunction "1_1") (pintype "passive"))
      (node (ref "R30") (pin "2") (pinfunction "2_2") (pintype "passive"))
      (node (ref "U$1") (pin "BB1") (pinfunction "1_BB1") (pintype "bidirectional"))
    )
    (net (code "70") (name "Net-(E18A-X)") (class "Default")
      (node (ref "E18") (pin "10") (pinfunction "X_10") (pintype "output"))
      (node (ref "E18") (pin "11") (pinfunction "X_11") (pintype "output"))
      (node (ref "R12") (pin "2") (pinfunction "2_2") (pintype "passive"))
    )
    (net (code "71") (name "Net-(E18A-~{X})") (class "Default")
      (node (ref "E18") (pin "12") (pinfunction "~{X}_12") (pintype "output"))
      (node (ref "E18") (pin "4") (pinfunction "A_4") (pintype "input"))
      (node (ref "E18") (pin "5") (pinfunction "B_5") (pintype "input"))
      (node (ref "E18") (pin "6") (pinfunction "C_6") (pintype "input"))
      (node (ref "E18") (pin "8") (pinfunction "D_8") (pintype "input"))
    )
    (net (code "72") (name "Net-(E18B-~{X})") (class "Default")
      (node (ref "E18") (pin "9") (pinfunction "~{X}_9") (pintype "output"))
      (node (ref "E2") (pin "13") (pinfunction "I2_13") (pintype "input"))
      (node (ref "E3") (pin "10") (pinfunction "I1_10") (pintype "input"))
      (node (ref "E3") (pin "9") (pinfunction "I0_9") (pintype "input"))
      (node (ref "R28") (pin "1") (pinfunction "1_1") (pintype "passive"))
    )
    (net (code "73") (name "Net-(E19A-D)") (class "Default")
      (node (ref "E19") (pin "2") (pinfunction "D_2") (pintype "input"))
      (node (ref "E19") (pin "9") (pinfunction "Q_9") (pintype "output"))
    )
    (net (code "74") (name "Net-(E21A-CLK)") (class "Default")
      (node (ref "E21") (pin "3") (pinfunction "CLK_3") (pintype "input"))
      (node (ref "E26") (pin "13") (pinfunction "O_13") (pintype "output"))
    )
    (net (code "75") (name "Net-(E21A-D)") (class "Default")
      (node (ref "E21") (pin "2") (pinfunction "D_2") (pintype "input"))
      (node (ref "E27") (pin "13") (pinfunction "O_13") (pintype "output"))
    )
    (net (code "76") (name "Net-(E21A-Q)") (class "Default")
      (node (ref "E21") (pin "5") (pinfunction "Q_5") (pintype "output"))
      (node (ref "E25") (pin "5") (pinfunction "I0_5") (pintype "input"))
    )
    (net (code "77") (name "Net-(E21B-CLR)") (class "Default")
      (node (ref "E21") (pin "13") (pinfunction "CLR_13") (pintype "input"))
      (node (ref "E22") (pin "6") (pinfunction "O_6") (pintype "output"))
    )
    (net (code "78") (name "Net-(E22B-I)") (class "Default")
      (node (ref "E22") (pin "3") (pinfunction "I_3") (pintype "input"))
      (node (ref "E26") (pin "10") (pinfunction "O_10") (pintype "output"))
    )
    (net (code "79") (name "Net-(E22C-I)") (class "Default")
      (node (ref "E22") (pin "5") (pinfunction "I_5") (pintype "input"))
      (node (ref "E29") (pin "8") (pinfunction "O_8") (pintype "output"))
    )
    (net (code "80") (name "Net-(E22D-I)") (class "Default")
      (node (ref "E22") (pin "9") (pinfunction "I_9") (pintype "input"))
      (node (ref "E28") (pin "3") (pinfunction "O_3") (pintype "output"))
      (node (ref "E32") (pin "2") (pinfunction "I0_2") (pintype "input"))
      (node (ref "E32") (pin "3") (pinfunction "I1_3") (pintype "input"))
    )
    (net (code "81") (name "Net-(E22E-I)") (class "Default")
      (node (ref "E22") (pin "11") (pinfunction "I_11") (pintype "input"))
      (node (ref "E36") (pin "8") (pinfunction "O_8") (pintype "output"))
    )
    (net (code "82") (name "Net-(E22F-I)") (class "Default")
      (node (ref "E22") (pin "13") (pinfunction "I_13") (pintype "input"))
      (node (ref "E3") (pin "11") (pinfunction "O_11") (pintype "output"))
    )
    (net (code "83") (name "Net-(E23A-O)") (class "Default")
      (node (ref "E23") (pin "3") (pinfunction "O_3") (pintype "output"))
      (node (ref "E28") (pin "10") (pinfunction "I4_10") (pintype "input"))
    )
    (net (code "84") (name "Net-(E23B-O)") (class "Default")
      (node (ref "E23") (pin "2") (pinfunction "O_2") (pintype "output"))
      (node (ref "E24") (pin "6") (pinfunction "I2_6") (pintype "input"))
    )
    (net (code "85") (name "Net-(E23C-O)") (class "Default")
      (node (ref "E23") (pin "14") (pinfunction "O_14") (pintype "output"))
      (node (ref "E24") (pin "9") (pinfunction "I3_9") (pintype "input"))
      (node (ref "E28") (pin "11") (pinfunction "I5_11") (pintype "input"))
    )
    (net (code "86") (name "Net-(E23D-O)") (class "Default")
      (node (ref "E23") (pin "13") (pinfunction "O_13") (pintype "output"))
      (node (ref "E24") (pin "10") (pinfunction "I4_10") (pintype "input"))
      (node (ref "E28") (pin "6") (pinfunction "I2_6") (pintype "input"))
    )
    (net (code "87") (name "Net-(E24A-I5)") (class "Default")
      (node (ref "E24") (pin "11") (pinfunction "I5_11") (pintype "input"))
      (node (ref "E35") (pin "2") (pinfunction "O_2") (pintype "output"))
    )
    (net (code "88") (name "Net-(E24A-O)") (class "Default")
      (node (ref "E24") (pin "3") (pinfunction "O_3") (pintype "output"))
      (node (ref "E32") (pin "5") (pinfunction "I0_5") (pintype "input"))
      (node (ref "E32") (pin "6") (pinfunction "I1_6") (pintype "input"))
      (node (ref "E32") (pin "8") (pinfunction "I0_8") (pintype "input"))
      (node (ref "E32") (pin "9") (pinfunction "I1_9") (pintype "input"))
    )
    (net (code "89") (name "Net-(E25A-O)") (class "Default")
      (node (ref "E25") (pin "1") (pinfunction "O_1") (pintype "output"))
      (node (ref "E33") (pin "11") (pinfunction "I0_11") (pintype "input"))
      (node (ref "E33") (pin "12") (pinfunction "I1_12") (pintype "input"))
    )
    (net (code "90") (name "Net-(E25B-O)") (class "Default")
      (node (ref "E25") (pin "4") (pinfunction "O_4") (pintype "output"))
      (node (ref "E33") (pin "2") (pinfunction "I0_2") (pintype "input"))
    )
    (net (code "91") (name "Net-(E25C-I1)") (class "Default")
      (node (ref "E25") (pin "9") (pinfunction "I1_9") (pintype "input"))
      (node (ref "E6") (pin "4") (pinfunction "O_4") (pintype "output"))
    )
    (net (code "92") (name "Net-(E25D-I0)") (class "Default")
      (node (ref "E25") (pin "11") (pinfunction "I0_11") (pintype "input"))
      (node (ref "E30") (pin "8") (pinfunction "O_8") (pintype "output"))
    )
    (net (code "93") (name "Net-(E25D-I1)") (class "Default")
      (node (ref "E25") (pin "12") (pinfunction "I1_12") (pintype "input"))
      (node (ref "E26") (pin "1") (pinfunction "O_1") (pintype "output"))
    )
    (net (code "94") (name "Net-(E26B-O)") (class "Default")
      (node (ref "E26") (pin "4") (pinfunction "O_4") (pintype "output"))
      (node (ref "E33") (pin "8") (pinfunction "I0_8") (pintype "input"))
      (node (ref "E33") (pin "9") (pinfunction "I1_9") (pintype "input"))
    )
    (net (code "95") (name "Net-(E29C-I1)") (class "Default")
      (node (ref "E29") (pin "10") (pinfunction "I1_10") (pintype "input"))
      (node (ref "E29") (pin "11") (pinfunction "O_11") (pintype "output"))
    )
    (net (code "96") (name "Net-(E34A-A)") (class "Default")
      (node (ref "E34") (pin "15") (pinfunction "A_15") (pintype "input"))
      (node (ref "E35") (pin "14") (pinfunction "O_14") (pintype "output"))
      (node (ref "E38") (pin "15") (pinfunction "A_15") (pintype "input"))
    )
    (net (code "97") (name "Net-(E34A-B)") (class "Default")
      (node (ref "E34") (pin "14") (pinfunction "B_14") (pintype "input"))
      (node (ref "E35") (pin "13") (pinfunction "O_13") (pintype "output"))
      (node (ref "E38") (pin "14") (pinfunction "B_14") (pintype "input"))
    )
    (net (code "98") (name "Net-(E34A-C)") (class "Default")
      (node (ref "E34") (pin "1") (pinfunction "C_1") (pintype "input"))
      (node (ref "E35") (pin "3") (pinfunction "O_3") (pintype "output"))
      (node (ref "E38") (pin "1") (pinfunction "C_1") (pintype "input"))
    )
    (net (code "99") (name "Net-(E36D-I0)") (class "Default")
      (node (ref "E36") (pin "1") (pinfunction "I0_1") (pintype "input"))
      (node (ref "E45") (pin "6") (pinfunction "~{Q}_6") (pintype "output"))
    )
    (net (code "100") (name "Net-(E36D-I1)") (class "Default")
      (node (ref "E36") (pin "2") (pinfunction "I1_2") (pintype "input"))
      (node (ref "E49") (pin "6") (pinfunction "~{Q}_6") (pintype "output"))
    )
    (net (code "101") (name "Net-(E36D-I2)") (class "Default")
      (node (ref "E36") (pin "3") (pinfunction "I2_3") (pintype "input"))
      (node (ref "E44") (pin "8") (pinfunction "~{Q}_8") (pintype "output"))
    )
    (net (code "102") (name "Net-(E36D-I3)") (class "Default")
      (node (ref "E36") (pin "4") (pinfunction "I3_4") (pintype "input"))
      (node (ref "E44") (pin "6") (pinfunction "~{Q}_6") (pintype "output"))
    )
    (net (code "103") (name "Net-(E36D-I4)") (class "Default")
      (node (ref "E36") (pin "5") (pinfunction "I4_5") (pintype "input"))
      (node (ref "E48") (pin "8") (pinfunction "~{Q}_8") (pintype "output"))
    )
    (net (code "104") (name "Net-(E36D-I5)") (class "Default")
      (node (ref "E36") (pin "6") (pinfunction "I5_6") (pintype "input"))
      (node (ref "E48") (pin "6") (pinfunction "~{Q}_6") (pintype "output"))
    )
    (net (code "105") (name "Net-(E36D-I7)") (class "Default")
      (node (ref "E36") (pin "12") (pinfunction "I7_12") (pintype "input"))
      (node (ref "E45") (pin "8") (pinfunction "~{Q}_8") (pintype "output"))
    )
    (net (code "106") (name "Net-(E37C-I0)") (class "Default")
      (node (ref "E37") (pin "1") (pinfunction "I0_1") (pintype "input"))
      (node (ref "E37") (pin "2") (pinfunction "I1_2") (pintype "input"))
      (node (ref "E37") (pin "4") (pinfunction "I2_4") (pintype "input"))
      (node (ref "E37") (pin "5") (pinfunction "I3_5") (pintype "input"))
      (node (ref "E6") (pin "6") (pinfunction "O_6") (pintype "output"))
    )
    (net (code "107") (name "Net-(E39A-I0)") (class "Default")
      (node (ref "E39") (pin "2") (pinfunction "I0_2") (pintype "input"))
      (node (ref "E40") (pin "5") (pinfunction "Q_5") (pintype "output"))
      (node (ref "E51") (pin "12") (pinfunction "D_12") (pintype "input"))
    )
    (net (code "108") (name "Net-(E39B-I0)") (class "Default")
      (node (ref "E39") (pin "5") (pinfunction "I0_5") (pintype "input"))
      (node (ref "E40") (pin "2") (pinfunction "D_2") (pintype "input"))
      (node (ref "E41") (pin "5") (pinfunction "Q_5") (pintype "output"))
    )
    (net (code "109") (name "Net-(E39C-I1)") (class "Default")
      (node (ref "E39") (pin "9") (pinfunction "I1_9") (pintype "input"))
      (node (ref "E41") (pin "2") (pinfunction "D_2") (pintype "input"))
      (node (ref "E41") (pin "9") (pinfunction "Q_9") (pintype "output"))
    )
    (net (code "110") (name "Net-(E39D-I1)") (class "Default")
      (node (ref "E39") (pin "12") (pinfunction "I1_12") (pintype "input"))
      (node (ref "E40") (pin "9") (pinfunction "Q_9") (pintype "output"))
      (node (ref "E41") (pin "12") (pinfunction "D_12") (pintype "input"))
    )
    (net (code "111") (name "Net-(E43A-O)") (class "Default")
      (node (ref "E43") (pin "3") (pinfunction "O_3") (pintype "output"))
      (node (ref "E45") (pin "4") (pinfunction "PRE_4") (pintype "input"))
    )
    (net (code "112") (name "Net-(E43B-O)") (class "Default")
      (node (ref "E43") (pin "2") (pinfunction "O_2") (pintype "output"))
      (node (ref "E44") (pin "4") (pinfunction "PRE_4") (pintype "input"))
    )
    (net (code "113") (name "Net-(E43C-O)") (class "Default")
      (node (ref "E43") (pin "14") (pinfunction "O_14") (pintype "output"))
      (node (ref "E44") (pin "10") (pinfunction "PRE_10") (pintype "input"))
    )
    (net (code "114") (name "Net-(E43D-O)") (class "Default")
      (node (ref "E43") (pin "13") (pinfunction "O_13") (pintype "output"))
      (node (ref "E45") (pin "10") (pinfunction "PRE_10") (pintype "input"))
    )
    (net (code "115") (name "Net-(E44A-D)") (class "Default")
      (node (ref "E44") (pin "2") (pinfunction "D_2") (pintype "input"))
      (node (ref "E45") (pin "5") (pinfunction "Q_5") (pintype "output"))
    )
    (net (code "116") (name "Net-(E44A-Q)") (class "Default")
      (node (ref "E44") (pin "12") (pinfunction "D_12") (pintype "input"))
      (node (ref "E44") (pin "5") (pinfunction "Q_5") (pintype "output"))
    )
    (net (code "117") (name "Net-(E44B-Q)") (class "Default")
      (node (ref "E44") (pin "9") (pinfunction "Q_9") (pintype "output"))
      (node (ref "E45") (pin "12") (pinfunction "D_12") (pintype "input"))
    )
    (net (code "118") (name "Net-(E45B-Q)") (class "Default")
      (node (ref "E45") (pin "9") (pinfunction "Q_9") (pintype "output"))
      (node (ref "E49") (pin "2") (pinfunction "D_2") (pintype "input"))
    )
    (net (code "119") (name "Net-(E46A-D)") (class "Default")
      (node (ref "E46") (pin "2") (pinfunction "D_2") (pintype "input"))
      (node (ref "E49") (pin "9") (pinfunction "Q_9") (pintype "output"))
    )
    (net (code "120") (name "Net-(E46A-Q)") (class "Default")
      (node (ref "E46") (pin "5") (pinfunction "Q_5") (pintype "output"))
      (node (ref "R21") (pin "1") (pinfunction "1_1") (pintype "passive"))
      (node (ref "R22") (pin "1") (pinfunction "1_1") (pintype "passive"))
      (node (ref "U$1") (pin "DB1") (pinfunction "1_DB1") (pintype "bidirectional"))
    )
    (net (code "121") (name "Net-(E46B-Q)") (class "Default")
      (node (ref "E46") (pin "9") (pinfunction "Q_9") (pintype "output"))
      (node (ref "U$1") (pin "DA1") (pinfunction "1_DA1") (pintype "bidirectional"))
    )
    (net (code "122") (name "Net-(E46B-~{Q})") (class "Default")
      (node (ref "E46") (pin "8") (pinfunction "~{Q}_8") (pintype "output"))
      (node (ref "Q2") (pin "2") (pinfunction "B_2") (pintype "passive"))
      (node (ref "R13") (pin "1") (pinfunction "1_1") (pintype "passive"))
    )
    (net (code "123") (name "Net-(E47A-O)") (class "Default")
      (node (ref "E47") (pin "3") (pinfunction "O_3") (pintype "output"))
      (node (ref "E49") (pin "4") (pinfunction "PRE_4") (pintype "input"))
    )
    (net (code "124") (name "Net-(E47B-O)") (class "Default")
      (node (ref "E47") (pin "2") (pinfunction "O_2") (pintype "output"))
      (node (ref "E48") (pin "4") (pinfunction "PRE_4") (pintype "input"))
    )
    (net (code "125") (name "Net-(E47C-O)") (class "Default")
      (node (ref "E47") (pin "14") (pinfunction "O_14") (pintype "output"))
      (node (ref "E48") (pin "10") (pinfunction "PRE_10") (pintype "input"))
    )
    (net (code "126") (name "Net-(E47D-O)") (class "Default")
      (node (ref "E47") (pin "13") (pinfunction "O_13") (pintype "output"))
      (node (ref "E49") (pin "10") (pinfunction "PRE_10") (pintype "input"))
    )
    (net (code "127") (name "Net-(E48A-D)") (class "Default")
      (node (ref "E48") (pin "2") (pinfunction "D_2") (pintype "input"))
      (node (ref "E49") (pin "5") (pinfunction "Q_5") (pintype "output"))
    )
    (net (code "128") (name "Net-(E48A-Q)") (class "Default")
      (node (ref "E48") (pin "12") (pinfunction "D_12") (pintype "input"))
      (node (ref "E48") (pin "5") (pinfunction "Q_5") (pintype "output"))
    )
    (net (code "129") (name "Net-(E48B-Q)") (class "Default")
      (node (ref "E48") (pin "9") (pinfunction "Q_9") (pintype "output"))
      (node (ref "E49") (pin "12") (pinfunction "D_12") (pintype "input"))
    )
    (net (code "130") (name "Net-(E50A-I0)") (class "Default")
      (node (ref "E50") (pin "2") (pinfunction "I0_2") (pintype "input"))
      (node (ref "E51") (pin "5") (pinfunction "Q_5") (pintype "output"))
    )
    (net (code "131") (name "Net-(E50B-I0)") (class "Default")
      (node (ref "E50") (pin "5") (pinfunction "I0_5") (pintype "input"))
      (node (ref "E51") (pin "2") (pinfunction "D_2") (pintype "input"))
      (node (ref "E52") (pin "5") (pinfunction "Q_5") (pintype "output"))
    )
    (net (code "132") (name "Net-(E50C-I1)") (class "Default")
      (node (ref "E50") (pin "9") (pinfunction "I1_9") (pintype "input"))
      (node (ref "E52") (pin "2") (pinfunction "D_2") (pintype "input"))
      (node (ref "E52") (pin "9") (pinfunction "Q_9") (pintype "output"))
    )
    (net (code "133") (name "Net-(E50D-I1)") (class "Default")
      (node (ref "E50") (pin "12") (pinfunction "I1_12") (pintype "input"))
      (node (ref "E51") (pin "9") (pinfunction "Q_9") (pintype "output"))
      (node (ref "E52") (pin "12") (pinfunction "D_12") (pintype "input"))
    )
    (net (code "134") (name "Net-(Q1-B)") (class "Default")
      (node (ref "C3") (pin "1") (pinfunction "1_1") (pintype "passive"))
      (node (ref "C4") (pin "1") (pinfunction "1_1") (pintype "passive"))
      (node (ref "Q1") (pin "2") (pinfunction "B_2") (pintype "passive"))
      (node (ref "R3") (pin "1") (pinfunction "1_1") (pintype "passive"))
      (node (ref "V3") (pin "1") (pinfunction "1_1") (pintype "passive"))
      (node (ref "V3") (pin "2") (pinfunction "2_2") (pintype "passive"))
    )
    (net (code "135") (name "Net-(Q1-E)") (class "Default")
      (node (ref "C4") (pin "2") (pinfunction "2_2") (pintype "passive"))
      (node (ref "C5") (pin "1") (pinfunction "1_1") (pintype "passive"))
      (node (ref "C6") (pin "1") (pinfunction "1_1") (pintype "passive"))
      (node (ref "Q1") (pin "1") (pinfunction "E_1") (pintype "passive"))
      (node (ref "R4") (pin "2") (pinfunction "2_2") (pintype "passive"))
      (node (ref "V4") (pin "1") (pinfunction "1_1") (pintype "passive"))
      (node (ref "V4") (pin "2") (pinfunction "2_2") (pintype "passive"))
    )
    (net (code "136") (name "Net-(Q2-E)") (class "Default")
      (node (ref "D4") (pin "C") (pinfunction "C_C") (pintype "passive"))
      (node (ref "Q2") (pin "1") (pinfunction "E_1") (pintype "passive"))
      (node (ref "R14") (pin "1") (pinfunction "1_1") (pintype "passive"))
    )
    (net (code "137") (name "Net-(Q3-B)") (class "Default")
      (node (ref "C13") (pin "1") (pinfunction "1_1") (pintype "passive"))
      (node (ref "Q3") (pin "2") (pinfunction "B_2") (pintype "passive"))
      (node (ref "R22") (pin "2") (pinfunction "2_2") (pintype "passive"))
    )
    (net (code "138") (name "Net-(R29-Pad2)") (class "Default")
      (node (ref "R29") (pin "2") (pinfunction "2_2") (pintype "passive"))
      (node (ref "R7") (pin "1") (pinfunction "1_1") (pintype "passive"))
      (node (ref "T1") (pin "16") (pinfunction "16_16") (pintype "passive"))
    )
    (net (code "139") (name "Net-(T1-Pad2)") (class "Default")
      (node (ref "T1") (pin "2") (pinfunction "2_2") (pintype "passive"))
      (node (ref "T1") (pin "3") (pinfunction "3_3") (pintype "passive"))
    )
    (net (code "140") (name "Net-(T1-Pad6)") (class "Default")
      (node (ref "T1") (pin "6") (pinfunction "6_6") (pintype "passive"))
      (node (ref "T1") (pin "7") (pinfunction "7_7") (pintype "passive"))
    )
    (net (code "141") (name "Net-(T1-Pad10)") (class "Default")
      (node (ref "T1") (pin "10") (pinfunction "10_10") (pintype "passive"))
      (node (ref "T1") (pin "11") (pinfunction "11_11") (pintype "passive"))
    )
    (net (code "142") (name "Net-(T1-Pad12)") (class "Default")
      (node (ref "T1") (pin "12") (pinfunction "12_12") (pintype "passive"))
      (node (ref "T1") (pin "13") (pinfunction "13_13") (pintype "passive"))
    )
    (net (code "143") (name "Net-(T1-Pad14)") (class "Default")
      (node (ref "T1") (pin "14") (pinfunction "14_14") (pintype "passive"))
      (node (ref "T1") (pin "15") (pinfunction "15_15") (pintype "passive"))
    )
    (net (code "144") (name "POWER_OK") (class "Default")
      (node (ref "E10") (pin "5") (pinfunction "I1_5") (pintype "input"))
      (node (ref "U$1") (pin "BV2") (pinfunction "1_BV2") (pintype "bidirectional"))
    )
    (net (code "145") (name "PRESET") (class "Default")
      (node (ref "E2") (pin "2") (pinfunction "I1_2") (pintype "input"))
      (node (ref "E6") (pin "2") (pinfunction "O_2") (pintype "output"))
    )
    (net (code "146") (name "RCVR_CLK") (class "Default")
      (node (ref "E12") (pin "3") (pinfunction "CLK_3") (pintype "input"))
      (node (ref "E13") (pin "9") (pinfunction "QB_9") (pintype "output"))
      (node (ref "E2") (pin "1") (pinfunction "I0_1") (pintype "input"))
    )
    (net (code "147") (name "READ_BUFFER") (class "Default")
      (node (ref "E30") (pin "6") (pinfunction "O_6") (pintype "output"))
      (node (ref "E31") (pin "5") (pinfunction "I0_5") (pintype "input"))
      (node (ref "E31") (pin "6") (pinfunction "I1_6") (pintype "input"))
      (node (ref "E39") (pin "11") (pinfunction "I0_11") (pintype "input"))
      (node (ref "E39") (pin "3") (pinfunction "I1_3") (pintype "input"))
      (node (ref "E39") (pin "6") (pinfunction "I1_6") (pintype "input"))
      (node (ref "E39") (pin "8") (pinfunction "I0_8") (pintype "input"))
      (node (ref "E50") (pin "11") (pinfunction "I0_11") (pintype "input"))
      (node (ref "E50") (pin "3") (pinfunction "I1_3") (pintype "input"))
      (node (ref "E50") (pin "6") (pinfunction "I1_6") (pintype "input"))
      (node (ref "E50") (pin "8") (pinfunction "I0_8") (pintype "input"))
    )
    (net (code "148") (name "RR_CLK") (class "Default")
      (node (ref "E40") (pin "8") (pinfunction "~{Q}_8") (pintype "output"))
      (node (ref "E46") (pin "11") (pinfunction "CLK_11") (pintype "input"))
    )
    (net (code "149") (name "RR_CTL") (class "Default")
      (node (ref "6") (pin "1") (pinfunction "P_1") (pintype "passive"))
      (node (ref "C9") (pin "1") (pinfunction "1_1") (pintype "passive"))
      (node (ref "D7") (pin "C") (pinfunction "C_C") (pintype "passive"))
      (node (ref "Q2") (pin "3") (pinfunction "C_3") (pintype "passive"))
    )
    (net (code "150") (name "RX_ACTIVE") (class "Default")
      (node (ref "C10") (pin "2") (pinfunction "2_2") (pintype "passive"))
      (node (ref "E1") (pin "13") (pinfunction "CLR_13") (pintype "input"))
      (node (ref "E1") (pin "5") (pinfunction "Q_5") (pintype "output"))
      (node (ref "E3") (pin "4") (pinfunction "I0_4") (pintype "input"))
      (node (ref "R15") (pin "1") (pinfunction "1_1") (pintype "passive"))
      (node (ref "U$1") (pin "AB1") (pinfunction "1_AB1") (pintype "bidirectional"))
    )
    (net (code "151") (name "RX_CLK") (class "Default")
      (node (ref "E12") (pin "11") (pinfunction "CLK_11") (pintype "input"))
      (node (ref "E2") (pin "10") (pinfunction "I1_10") (pintype "input"))
      (node (ref "E37") (pin "6") (pinfunction "O_6") (pintype "output"))
      (node (ref "E40") (pin "11") (pinfunction "CLK_11") (pintype "input"))
      (node (ref "E40") (pin "3") (pinfunction "CLK_3") (pintype "input"))
      (node (ref "E41") (pin "11") (pinfunction "CLK_11") (pintype "input"))
      (node (ref "E41") (pin "3") (pinfunction "CLK_3") (pintype "input"))
      (node (ref "E42") (pin "11") (pinfunction "CLK_11") (pintype "input"))
      (node (ref "E51") (pin "11") (pinfunction "CLK_11") (pintype "input"))
      (node (ref "E51") (pin "3") (pinfunction "CLK_3") (pintype "input"))
      (node (ref "E52") (pin "11") (pinfunction "CLK_11") (pintype "input"))
      (node (ref "E52") (pin "3") (pinfunction "CLK_3") (pintype "input"))
    )
    (net (code "152") (name "RX_DATA") (class "Default")
      (node (ref "E2") (pin "11") (pinfunction "I2_11") (pintype "input"))
      (node (ref "E3") (pin "8") (pinfunction "O_8") (pintype "output"))
      (node (ref "E40") (pin "12") (pinfunction "D_12") (pintype "input"))
    )
    (net (code "153") (name "TP3") (class "Default")
      (node (ref "E27") (pin "4") (pinfunction "I0_4") (pintype "input"))
      (node (ref "U$1") (pin "CH2") (pinfunction "1_CH2") (pintype "bidirectional"))
    )
    (net (code "154") (name "VCC") (class "Default")
      (node (ref "C1") (pin "+") (pinfunction "+_+") (pintype "passive"))
      (node (ref "C17") (pin "+") (pinfunction "+_+") (pintype "passive"))
      (node (ref "C18") (pin "+") (pinfunction "+_+") (pintype "passive"))
      (node (ref "C19") (pin "+") (pinfunction "+_+") (pintype "passive"))
      (node (ref "C2") (pin "1") (pinfunction "1_1") (pintype "passive"))
      (node (ref "C20") (pin "1") (pinfunction "1_1") (pintype "passive"))
      (node (ref "C21") (pin "1") (pinfunction "1_1") (pintype "passive"))
      (node (ref "C22") (pin "1") (pinfunction "1_1") (pintype "passive"))
      (node (ref "C23") (pin "1") (pinfunction "1_1") (pintype "passive"))
      (node (ref "C24") (pin "1") (pinfunction "1_1") (pintype "passive"))
      (node (ref "C25") (pin "1") (pinfunction "1_1") (pintype "passive"))
      (node (ref "C26") (pin "1") (pinfunction "1_1") (pintype "passive"))
      (node (ref "C27") (pin "1") (pinfunction "1_1") (pintype "passive"))
      (node (ref "C28") (pin "1") (pinfunction "1_1") (pintype "passive"))
      (node (ref "C29") (pin "1") (pinfunction "1_1") (pintype "passive"))
      (node (ref "C30") (pin "1") (pinfunction "1_1") (pintype "passive"))
      (node (ref "C31") (pin "1") (pinfunction "1_1") (pintype "passive"))
      (node (ref "C32") (pin "1") (pinfunction "1_1") (pintype "passive"))
      (node (ref "C33") (pin "1") (pinfunction "1_1") (pintype "passive"))
      (node (ref "C34") (pin "1") (pinfunction "1_1") (pintype "passive"))
      (node (ref "C35") (pin "1") (pinfunction "1_1") (pintype "passive"))
      (node (ref "C36") (pin "1") (pinfunction "1_1") (pintype "passive"))
      (node (ref "C37") (pin "1") (pinfunction "1_1") (pintype "passive"))
      (node (ref "C38") (pin "1") (pinfunction "1_1") (pintype "passive"))
      (node (ref "C39") (pin "1") (pinfunction "1_1") (pintype "passive"))
      (node (ref "C40") (pin "1") (pinfunction "1_1") (pintype "passive"))
      (node (ref "C41") (pin "1") (pinfunction "1_1") (pintype "passive"))
      (node (ref "C42") (pin "1") (pinfunction "1_1") (pintype "passive"))
      (node (ref "C43") (pin "1") (pinfunction "1_1") (pintype "passive"))
      (node (ref "C44") (pin "1") (pinfunction "1_1") (pintype "passive"))
      (node (ref "C45") (pin "1") (pinfunction "1_1") (pintype "passive"))
      (node (ref "C46") (pin "1") (pinfunction "1_1") (pintype "passive"))
      (node (ref "C47") (pin "1") (pinfunction "1_1") (pintype "passive"))
      (node (ref "C48") (pin "1") (pinfunction "1_1") (pintype "passive"))
      (node (ref "C49") (pin "1") (pinfunction "1_1") (pintype "passive"))
      (node (ref "C50") (pin "1") (pinfunction "1_1") (pintype "passive"))
      (node (ref "C51") (pin "1") (pinfunction "1_1") (pintype "passive"))
      (node (ref "C52") (pin "1") (pinfunction "1_1") (pintype "passive"))
      (node (ref "C53") (pin "1") (pinfunction "1_1") (pintype "passive"))
      (node (ref "C54") (pin "1") (pinfunction "1_1") (pintype "passive"))
      (node (ref "C55") (pin "1") (pinfunction "1_1") (pintype "passive"))
      (node (ref "C56") (pin "1") (pinfunction "1_1") (pintype "passive"))
      (node (ref "C57") (pin "1") (pinfunction "1_1") (pintype "passive"))
      (node (ref "C58") (pin "1") (pinfunction "1_1") (pintype "passive"))
      (node (ref "C59") (pin "1") (pinfunction "1_1") (pintype "passive"))
      (node (ref "C60") (pin "1") (pinfunction "1_1") (pintype "passive"))
      (node (ref "C61") (pin "1") (pinfunction "1_1") (pintype "passive"))
      (node (ref "C62") (pin "1") (pinfunction "1_1") (pintype "passive"))
      (node (ref "C63") (pin "1") (pinfunction "1_1") (pintype "passive"))
      (node (ref "C64") (pin "1") (pinfunction "1_1") (pintype "passive"))
      (node (ref "C65") (pin "1") (pinfunction "1_1") (pintype "passive"))
      (node (ref "C66") (pin "1") (pinfunction "1_1") (pintype "passive"))
      (node (ref "C67") (pin "1") (pinfunction "1_1") (pintype "passive"))
      (node (ref "C68") (pin "1") (pinfunction "1_1") (pintype "passive"))
      (node (ref "C69") (pin "1") (pinfunction "1_1") (pintype "passive"))
      (node (ref "C70") (pin "1") (pinfunction "1_1") (pintype "passive"))
      (node (ref "C71") (pin "1") (pinfunction "1_1") (pintype "passive"))
      (node (ref "D2") (pin "C") (pinfunction "C_C") (pintype "passive"))
      (node (ref "D9") (pin "C") (pinfunction "C_C") (pintype "passive"))
      (node (ref "Q1") (pin "3") (pinfunction "C_3") (pintype "passive"))
      (node (ref "R1") (pin "2") (pinfunction "2_2") (pintype "passive"))
      (node (ref "R11") (pin "2") (pinfunction "2_2") (pintype "passive"))
      (node (ref "R13") (pin "2") (pinfunction "2_2") (pintype "passive"))
      (node (ref "R14") (pin "2") (pinfunction "2_2") (pintype "passive"))
      (node (ref "R15") (pin "2") (pinfunction "2_2") (pintype "passive"))
      (node (ref "R17") (pin "2") (pinfunction "2_2") (pintype "passive"))
      (node (ref "R18") (pin "2") (pinfunction "2_2") (pintype "passive"))
      (node (ref "R20") (pin "2") (pinfunction "2_2") (pintype "passive"))
      (node (ref "R21") (pin "2") (pinfunction "2_2") (pintype "passive"))
      (node (ref "R26") (pin "2") (pinfunction "2_2") (pintype "passive"))
      (node (ref "R28") (pin "2") (pinfunction "2_2") (pintype "passive"))
      (node (ref "R3") (pin "2") (pinfunction "2_2") (pintype "passive"))
      (node (ref "R5") (pin "2") (pinfunction "2_2") (pintype "passive"))
      (node (ref "R6") (pin "2") (pinfunction "2_2") (pintype "passive"))
      (node (ref "R8") (pin "2") (pinfunction "2_2") (pintype "passive"))
      (node (ref "R9") (pin "2") (pinfunction "2_2") (pintype "passive"))
      (node (ref "U$1") (pin "AA2") (pinfunction "1_AA2") (pintype "bidirectional"))
      (node (ref "U$1") (pin "BA2") (pinfunction "1_BA2") (pintype "bidirectional"))
      (node (ref "U$1") (pin "CA2") (pinfunction "1_CA2") (pintype "bidirectional"))
    )
    (net (code "155") (name "XMIT_ACTIVE") (class "Default")
      (node (ref "E15") (pin "2") (pinfunction "D_2") (pintype "input"))
      (node (ref "E15") (pin "9") (pinfunction "Q_9") (pintype "output"))
      (node (ref "E16") (pin "13") (pinfunction "I1_13") (pintype "input"))
      (node (ref "E17") (pin "10") (pinfunction "I1_10") (pintype "input"))
      (node (ref "E46") (pin "4") (pinfunction "PRE_4") (pintype "input"))
      (node (ref "U$1") (pin "BA1") (pinfunction "1_BA1") (pintype "bidirectional"))
    )
    (net (code "156") (name "XMIT_CLK") (class "Default")
      (node (ref "E13") (pin "11") (pinfunction "QD_11") (pintype "output"))
      (node (ref "E15") (pin "11") (pinfunction "CLK_11") (pintype "input"))
      (node (ref "E15") (pin "3") (pinfunction "CLK_3") (pintype "input"))
      (node (ref "E19") (pin "11") (pinfunction "CLK_11") (pintype "input"))
      (node (ref "E19") (pin "3") (pinfunction "CLK_3") (pintype "input"))
      (node (ref "E20") (pin "3") (pinfunction "CLK_3") (pintype "input"))
    )
    (net (code "157") (name "unconnected-(E1B-~{Q}-Pad8)") (class "Default")
      (node (ref "E1") (pin "8") (pinfunction "~{Q}_8") (pintype "output"))
    )
    (net (code "158") (name "unconnected-(E4A-QB-Pad9)") (class "Default")
      (node (ref "E4") (pin "9") (pinfunction "QB_9") (pintype "output"))
    )
    (net (code "159") (name "unconnected-(E4A-QC-Pad8)") (class "Default")
      (node (ref "E4") (pin "8") (pinfunction "QC_8") (pintype "output"))
    )
    (net (code "160") (name "unconnected-(E5A-CKA-Pad14)") (class "Default")
      (node (ref "E5") (pin "14") (pinfunction "CKA_14") (pintype "input"))
    )
    (net (code "161") (name "unconnected-(E5A-QA-Pad12)") (class "Default")
      (node (ref "E5") (pin "12") (pinfunction "QA_12") (pintype "output"))
    )
    (net (code "162") (name "unconnected-(E5A-QB-Pad9)") (class "Default")
      (node (ref "E5") (pin "9") (pinfunction "QB_9") (pintype "output"))
    )
    (net (code "163") (name "unconnected-(E5A-QC-Pad8)") (class "Default")
      (node (ref "E5") (pin "8") (pinfunction "QC_8") (pintype "output"))
    )
    (net (code "164") (name "unconnected-(E7B-Q-Pad9)") (class "Default")
      (node (ref "E7") (pin "9") (pinfunction "Q_9") (pintype "output"))
    )
    (net (code "165") (name "unconnected-(E8A-QB-Pad9)") (class "Default")
      (node (ref "E8") (pin "9") (pinfunction "QB_9") (pintype "output"))
    )
    (net (code "166") (name "unconnected-(E8A-QC-Pad8)") (class "Default")
      (node (ref "E8") (pin "8") (pinfunction "QC_8") (pintype "output"))
    )
    (net (code "167") (name "unconnected-(E9A-CLR-Pad2)") (class "Default")
      (node (ref "E9") (pin "2") (pinfunction "CLR_2") (pintype "input"))
    )
    (net (code "168") (name "unconnected-(E9A-PRE-Pad13)") (class "Default")
      (node (ref "E9") (pin "13") (pinfunction "PRE_13") (pintype "input"))
    )
    (net (code "169") (name "unconnected-(E13A-QC-Pad8)") (class "Default")
      (node (ref "E13") (pin "8") (pinfunction "QC_8") (pintype "output"))
    )
    (net (code "170") (name "unconnected-(E19A-Q-Pad5)") (class "Default")
      (node (ref "E19") (pin "5") (pinfunction "Q_5") (pintype "output"))
    )
    (net (code "171") (name "unconnected-(E19B-~{Q}-Pad8)") (class "Default")
      (node (ref "E19") (pin "8") (pinfunction "~{Q}_8") (pintype "output"))
    )
    (net (code "172") (name "unconnected-(E21B-Q-Pad9)") (class "Default")
      (node (ref "E21") (pin "9") (pinfunction "Q_9") (pintype "output"))
    )
    (net (code "173") (name "unconnected-(E34A-3-Pad10)") (class "Default")
      (node (ref "E34") (pin "10") (pinfunction "3_10") (pintype "output"))
    )
    (net (code "174") (name "unconnected-(E34A-7-Pad5)") (class "Default")
      (node (ref "E34") (pin "5") (pinfunction "7_5") (pintype "output"))
    )
    (net (code "175") (name "unconnected-(E34A-8-Pad6)") (class "Default")
      (node (ref "E34") (pin "6") (pinfunction "8_6") (pintype "output"))
    )
    (net (code "176") (name "unconnected-(E34A-9-Pad7)") (class "Default")
      (node (ref "E34") (pin "7") (pinfunction "9_7") (pintype "output"))
    )
    (net (code "177") (name "unconnected-(E38A-3-Pad10)") (class "Default")
      (node (ref "E38") (pin "10") (pinfunction "3_10") (pintype "output"))
    )
    (net (code "178") (name "unconnected-(E38A-7-Pad5)") (class "Default")
      (node (ref "E38") (pin "5") (pinfunction "7_5") (pintype "output"))
    )
    (net (code "179") (name "unconnected-(E38A-8-Pad6)") (class "Default")
      (node (ref "E38") (pin "6") (pinfunction "8_6") (pintype "output"))
    )
    (net (code "180") (name "unconnected-(E38A-9-Pad7)") (class "Default")
      (node (ref "E38") (pin "7") (pinfunction "9_7") (pintype "output"))
    )
    (net (code "181") (name "unconnected-(E40A-~{Q}-Pad6)") (class "Default")
      (node (ref "E40") (pin "6") (pinfunction "~{Q}_6") (pintype "output"))
    )
    (net (code "182") (name "unconnected-(E41A-~{Q}-Pad6)") (class "Default")
      (node (ref "E41") (pin "6") (pinfunction "~{Q}_6") (pintype "output"))
    )
    (net (code "183") (name "unconnected-(E41B-~{Q}-Pad8)") (class "Default")
      (node (ref "E41") (pin "8") (pinfunction "~{Q}_8") (pintype "output"))
    )
    (net (code "184") (name "unconnected-(E42B-Q-Pad9)") (class "Default")
      (node (ref "E42") (pin "9") (pinfunction "Q_9") (pintype "output"))
    )
    (net (code "185") (name "unconnected-(E46A-~{Q}-Pad6)") (class "Default")
      (node (ref "E46") (pin "6") (pinfunction "~{Q}_6") (pintype "output"))
    )
    (net (code "186") (name "unconnected-(E49B-~{Q}-Pad8)") (class "Default")
      (node (ref "E49") (pin "8") (pinfunction "~{Q}_8") (pintype "output"))
    )
    (net (code "187") (name "unconnected-(E51B-~{Q}-Pad8)") (class "Default")
      (node (ref "E51") (pin "8") (pinfunction "~{Q}_8") (pintype "output"))
    )
    (net (code "188") (name "unconnected-(E52A-~{Q}-Pad6)") (class "Default")
      (node (ref "E52") (pin "6") (pinfunction "~{Q}_6") (pintype "output"))
    )
    (net (code "189") (name "unconnected-(E52B-~{Q}-Pad8)") (class "Default")
      (node (ref "E52") (pin "8") (pinfunction "~{Q}_8") (pintype "output"))
    )
    (net (code "190") (name "~{603}") (class "Default")
      (node (ref "E22") (pin "8") (pinfunction "O_8") (pintype "output"))
      (node (ref "E34") (pin "2") (pinfunction "D_2") (pintype "input"))
    )
    (net (code "191") (name "~{604}") (class "Default")
      (node (ref "E32") (pin "10") (pinfunction "O_10") (pintype "open_collector"))
      (node (ref "E38") (pin "2") (pinfunction "D_2") (pintype "input"))
      (node (ref "R9") (pin "1") (pinfunction "1_1") (pintype "passive"))
    )
    (net (code "192") (name "~{C0}") (class "Default")
      (node (ref "E31") (pin "10") (pinfunction "O_10") (pintype "open_collector"))
      (node (ref "U$1") (pin "CE1") (pinfunction "1_CE1") (pintype "bidirectional"))
    )
    (net (code "193") (name "~{C1}") (class "Default")
      (node (ref "E31") (pin "1") (pinfunction "O_1") (pintype "open_collector"))
      (node (ref "E31") (pin "4") (pinfunction "O_4") (pintype "open_collector"))
      (node (ref "U$1") (pin "CH1") (pinfunction "1_CH1") (pintype "bidirectional"))
    )
    (net (code "194") (name "~{CLR_ACTIVE}") (class "Default")
      (node (ref "E1") (pin "1") (pinfunction "CLR_1") (pintype "input"))
      (node (ref "E25") (pin "10") (pinfunction "O_10") (pintype "output"))
    )
    (net (code "195") (name "~{DATA4}") (class "Default")
      (node (ref "E39") (pin "13") (pinfunction "O_13") (pintype "open_collector"))
      (node (ref "E43") (pin "4") (pinfunction "I0_4") (pintype "input"))
      (node (ref "U$1") (pin "BR1") (pinfunction "1_BR1") (pintype "bidirectional"))
    )
    (net (code "196") (name "~{DATA5}") (class "Default")
      (node (ref "E39") (pin "10") (pinfunction "O_10") (pintype "open_collector"))
      (node (ref "E43") (pin "6") (pinfunction "I0_6") (pintype "input"))
      (node (ref "U$1") (pin "BS1") (pinfunction "1_BS1") (pintype "bidirectional"))
    )
    (net (code "197") (name "~{DATA6}") (class "Default")
      (node (ref "E39") (pin "4") (pinfunction "O_4") (pintype "open_collector"))
      (node (ref "E43") (pin "9") (pinfunction "I0_9") (pintype "input"))
      (node (ref "U$1") (pin "BU1") (pinfunction "1_BU1") (pintype "bidirectional"))
    )
    (net (code "198") (name "~{DATA7}") (class "Default")
      (node (ref "E39") (pin "1") (pinfunction "O_1") (pintype "open_collector"))
      (node (ref "E43") (pin "12") (pinfunction "I1_12") (pintype "input"))
      (node (ref "U$1") (pin "BV1") (pinfunction "1_BV1") (pintype "bidirectional"))
    )
    (net (code "199") (name "~{DATA8}") (class "Default")
      (node (ref "E47") (pin "4") (pinfunction "I0_4") (pintype "input"))
      (node (ref "E50") (pin "13") (pinfunction "O_13") (pintype "open_collector"))
      (node (ref "U$1") (pin "DR1") (pinfunction "1_DR1") (pintype "bidirectional"))
    )
    (net (code "200") (name "~{DATA9}") (class "Default")
      (node (ref "E47") (pin "6") (pinfunction "I0_6") (pintype "input"))
      (node (ref "E50") (pin "10") (pinfunction "O_10") (pintype "open_collector"))
      (node (ref "U$1") (pin "DS1") (pinfunction "1_DS1") (pintype "bidirectional"))
    )
    (net (code "201") (name "~{DATA10}") (class "Default")
      (node (ref "E47") (pin "9") (pinfunction "I0_9") (pintype "input"))
      (node (ref "E50") (pin "4") (pinfunction "O_4") (pintype "open_collector"))
      (node (ref "U$1") (pin "DU1") (pinfunction "1_DU1") (pintype "bidirectional"))
    )
    (net (code "202") (name "~{DATA11}") (class "Default")
      (node (ref "E27") (pin "12") (pinfunction "I1_12") (pintype "input"))
      (node (ref "E47") (pin "12") (pinfunction "I1_12") (pintype "input"))
      (node (ref "E50") (pin "1") (pinfunction "O_1") (pintype "open_collector"))
      (node (ref "U$1") (pin "DV1") (pinfunction "1_DV1") (pintype "bidirectional"))
    )
    (net (code "203") (name "~{DTX_ACTIVE}") (class "Default")
      (node (ref "E46") (pin "1") (pinfunction "CLR_1") (pintype "input"))
      (node (ref "E6") (pin "12") (pinfunction "O_12") (pintype "output"))
    )
    (net (code "204") (name "~{ENABLE}") (class "Default")
      (node (ref "E36") (pin "11") (pinfunction "I6_11") (pintype "input"))
      (node (ref "E42") (pin "6") (pinfunction "~{Q}_6") (pintype "output"))
    )
    (net (code "205") (name "~{FREQ_DIV}") (class "Default")
      (node (ref "E15") (pin "4") (pinfunction "PRE_4") (pintype "input"))
      (node (ref "E19") (pin "10") (pinfunction "PRE_10") (pintype "input"))
      (node (ref "E19") (pin "4") (pinfunction "PRE_4") (pintype "input"))
      (node (ref "E21") (pin "11") (pinfunction "CLK_11") (pintype "input"))
      (node (ref "E37") (pin "8") (pinfunction "O_8") (pintype "output"))
      (node (ref "E42") (pin "3") (pinfunction "CLK_3") (pintype "input"))
      (node (ref "E44") (pin "11") (pinfunction "CLK_11") (pintype "input"))
      (node (ref "E44") (pin "3") (pinfunction "CLK_3") (pintype "input"))
      (node (ref "E45") (pin "11") (pinfunction "CLK_11") (pintype "input"))
      (node (ref "E45") (pin "3") (pinfunction "CLK_3") (pintype "input"))
      (node (ref "E46") (pin "3") (pinfunction "CLK_3") (pintype "input"))
      (node (ref "E48") (pin "11") (pinfunction "CLK_11") (pintype "input"))
      (node (ref "E48") (pin "3") (pinfunction "CLK_3") (pintype "input"))
      (node (ref "E49") (pin "11") (pinfunction "CLK_11") (pintype "input"))
      (node (ref "E49") (pin "3") (pinfunction "CLK_3") (pintype "input"))
    )
    (net (code "206") (name "~{INITIALIZE}") (class "Default")
      (node (ref "E11") (pin "6") (pinfunction "O_6") (pintype "output"))
      (node (ref "E15") (pin "13") (pinfunction "CLR_13") (pintype "input"))
      (node (ref "E20") (pin "4") (pinfunction "PRE_4") (pintype "input"))
      (node (ref "E21") (pin "1") (pinfunction "CLR_1") (pintype "input"))
      (node (ref "E29") (pin "9") (pinfunction "I0_9") (pintype "input"))
      (node (ref "E30") (pin "9") (pinfunction "I0_9") (pintype "input"))
      (node (ref "E42") (pin "1") (pinfunction "CLR_1") (pintype "input"))
      (node (ref "E44") (pin "1") (pinfunction "CLR_1") (pintype "input"))
      (node (ref "E44") (pin "13") (pinfunction "CLR_13") (pintype "input"))
      (node (ref "E45") (pin "1") (pinfunction "CLR_1") (pintype "input"))
      (node (ref "E45") (pin "13") (pinfunction "CLR_13") (pintype "input"))
      (node (ref "E46") (pin "13") (pinfunction "CLR_13") (pintype "input"))
      (node (ref "E48") (pin "1") (pinfunction "CLR_1") (pintype "input"))
      (node (ref "E48") (pin "13") (pinfunction "CLR_13") (pintype "input"))
      (node (ref "E49") (pin "1") (pinfunction "CLR_1") (pintype "input"))
      (node (ref "E49") (pin "13") (pinfunction "CLR_13") (pintype "input"))
    )
    (net (code "207") (name "~{INTERNAL_IO}") (class "Default")
      (node (ref "E32") (pin "1") (pinfunction "O_1") (pintype "open_collector"))
      (node (ref "E32") (pin "4") (pinfunction "O_4") (pintype "open_collector"))
      (node (ref "U$1") (pin "CL1") (pinfunction "1_CL1") (pintype "bidirectional"))
    )
    (net (code "208") (name "~{INT_RQST}") (class "Default")
      (node (ref "E33") (pin "4") (pinfunction "O_4") (pintype "open_collector"))
      (node (ref "U$1") (pin "CP1") (pinfunction "1_CP1") (pintype "bidirectional"))
    )
    (net (code "209") (name "~{IO_PAUSE}") (class "Default")
      (node (ref "E27") (pin "7") (pinfunction "I1_7") (pintype "input"))
      (node (ref "U$1") (pin "CD1") (pinfunction "1_CD1") (pintype "bidirectional"))
    )
    (net (code "210") (name "~{KCC}") (class "Default")
      (node (ref "E30") (pin "2") (pinfunction "I1_2") (pintype "input"))
      (node (ref "E34") (pin "11") (pinfunction "2_11") (pintype "output"))
    )
    (net (code "211") (name "~{KCF}") (class "Default")
      (node (ref "E26") (pin "2") (pinfunction "I0_2") (pintype "input"))
      (node (ref "E34") (pin "13") (pinfunction "0_13") (pintype "output"))
    )
    (net (code "212") (name "~{KIE}") (class "Default")
      (node (ref "E26") (pin "12") (pinfunction "I1_12") (pintype "input"))
      (node (ref "E34") (pin "3") (pinfunction "5_3") (pintype "output"))
    )
    (net (code "213") (name "~{KRB}") (class "Default")
      (node (ref "E30") (pin "1") (pinfunction "I0_1") (pintype "input"))
      (node (ref "E30") (pin "5") (pinfunction "I1_5") (pintype "input"))
      (node (ref "E34") (pin "4") (pinfunction "6_4") (pintype "output"))
    )
    (net (code "214") (name "~{KRS}") (class "Default")
      (node (ref "E30") (pin "4") (pinfunction "I0_4") (pintype "input"))
      (node (ref "E34") (pin "9") (pinfunction "4_9") (pintype "output"))
    )
    (net (code "215") (name "~{KSF}") (class "Default")
      (node (ref "E26") (pin "6") (pinfunction "I1_6") (pintype "input"))
      (node (ref "E34") (pin "12") (pinfunction "1_12") (pintype "output"))
    )
    (net (code "216") (name "~{LAST_UNIT}") (class "Default")
      (node (ref "E12") (pin "8") (pinfunction "~{Q}_8") (pintype "output"))
      (node (ref "E2") (pin "3") (pinfunction "I0_3") (pintype "input"))
    )
    (net (code "217") (name "~{MD3}") (class "Default")
      (node (ref "E10") (pin "7") (pinfunction "I1_7") (pintype "input"))
      (node (ref "U$1") (pin "AP1") (pinfunction "1_AP1") (pintype "bidirectional"))
    )
    (net (code "218") (name "~{MD4}") (class "Default")
      (node (ref "E23") (pin "12") (pinfunction "I1_12") (pintype "input"))
      (node (ref "U$1") (pin "BK1") (pinfunction "1_BK1") (pintype "bidirectional"))
    )
    (net (code "219") (name "~{MD5}") (class "Default")
      (node (ref "E23") (pin "9") (pinfunction "I0_9") (pintype "input"))
      (node (ref "U$1") (pin "BL1") (pinfunction "1_BL1") (pintype "bidirectional"))
    )
    (net (code "220") (name "~{MD6}") (class "Default")
      (node (ref "E23") (pin "4") (pinfunction "I0_4") (pintype "input"))
      (node (ref "E24") (pin "5") (pinfunction "I1_5") (pintype "input"))
      (node (ref "U$1") (pin "BM1") (pinfunction "1_BM1") (pintype "bidirectional"))
    )
    (net (code "221") (name "~{MD7}") (class "Default")
      (node (ref "E23") (pin "7") (pinfunction "I1_7") (pintype "input"))
      (node (ref "E28") (pin "9") (pinfunction "I3_9") (pintype "input"))
      (node (ref "U$1") (pin "BP1") (pinfunction "1_BP1") (pintype "bidirectional"))
    )
    (net (code "222") (name "~{MD8}") (class "Default")
      (node (ref "E28") (pin "4") (pinfunction "I0_4") (pintype "input"))
      (node (ref "E35") (pin "7") (pinfunction "I1_7") (pintype "input"))
      (node (ref "U$1") (pin "DK1") (pinfunction "1_DK1") (pintype "bidirectional"))
    )
    (net (code "223") (name "~{MD9}") (class "Default")
      (node (ref "E35") (pin "4") (pinfunction "I0_4") (pintype "input"))
      (node (ref "U$1") (pin "DL1") (pinfunction "1_DL1") (pintype "bidirectional"))
    )
    (net (code "224") (name "~{MD10}") (class "Default")
      (node (ref "E35") (pin "12") (pinfunction "I1_12") (pintype "input"))
      (node (ref "U$1") (pin "DM1") (pinfunction "1_DM1") (pintype "bidirectional"))
    )
    (net (code "225") (name "~{MD11}") (class "Default")
      (node (ref "E35") (pin "9") (pinfunction "I0_9") (pintype "input"))
      (node (ref "U$1") (pin "DP1") (pinfunction "1_DP1") (pintype "bidirectional"))
    )
    (net (code "226") (name "~{POWER_OK}") (class "Default")
      (node (ref "E10") (pin "3") (pinfunction "O_3") (pintype "output"))
      (node (ref "E25") (pin "8") (pinfunction "I0_8") (pintype "input"))
    )
    (net (code "227") (name "~{PRESET}") (class "Default")
      (node (ref "E2") (pin "6") (pinfunction "O_6") (pintype "output"))
      (node (ref "E3") (pin "1") (pinfunction "I0_1") (pintype "input"))
      (node (ref "E6") (pin "1") (pinfunction "I_1") (pintype "input"))
      (node (ref "E7") (pin "1") (pinfunction "CLR_1") (pintype "input"))
      (node (ref "E7") (pin "13") (pinfunction "CLR_13") (pintype "input"))
    )
    (net (code "228") (name "~{RX_ACTIVE}") (class "Default")
      (node (ref "E1") (pin "6") (pinfunction "~{Q}_6") (pintype "output"))
      (node (ref "E17") (pin "13") (pinfunction "I1_13") (pintype "input"))
      (node (ref "E2") (pin "4") (pinfunction "I1_4") (pintype "input"))
      (node (ref "E2") (pin "5") (pinfunction "I2_5") (pintype "input"))
    )
    (net (code "229") (name "~{RX_CLK}") (class "Default")
      (node (ref "E1") (pin "11") (pinfunction "CLK_11") (pintype "input"))
      (node (ref "E3") (pin "12") (pinfunction "I0_12") (pintype "input"))
      (node (ref "E3") (pin "6") (pinfunction "O_6") (pintype "output"))
      (node (ref "E6") (pin "9") (pinfunction "I_9") (pintype "input"))
    )
    (net (code "230") (name "~{RX_CLR}") (class "Default")
      (node (ref "E1") (pin "10") (pinfunction "PRE_10") (pintype "input"))
      (node (ref "E11") (pin "8") (pinfunction "O_8") (pintype "output"))
      (node (ref "E40") (pin "10") (pinfunction "PRE_10") (pintype "input"))
      (node (ref "E40") (pin "4") (pinfunction "PRE_4") (pintype "input"))
      (node (ref "E41") (pin "10") (pinfunction "PRE_10") (pintype "input"))
      (node (ref "E41") (pin "4") (pinfunction "PRE_4") (pintype "input"))
      (node (ref "E51") (pin "10") (pinfunction "PRE_10") (pintype "input"))
      (node (ref "E51") (pin "4") (pinfunction "PRE_4") (pintype "input"))
      (node (ref "E52") (pin "10") (pinfunction "PRE_10") (pintype "input"))
      (node (ref "E52") (pin "4") (pinfunction "PRE_4") (pintype "input"))
    )
    (net (code "231") (name "~{RX_FLAG}") (class "Default")
      (node (ref "E17") (pin "4") (pinfunction "I0_4") (pintype "input"))
      (node (ref "E26") (pin "5") (pinfunction "I0_5") (pintype "input"))
      (node (ref "E42") (pin "8") (pinfunction "~{Q}_8") (pintype "output"))
    )
    (net (code "232") (name "~{SET_RR}") (class "Default")
      (node (ref "E30") (pin "10") (pinfunction "I1_10") (pintype "input"))
      (node (ref "E30") (pin "11") (pinfunction "O_11") (pintype "output"))
      (node (ref "E46") (pin "10") (pinfunction "PRE_10") (pintype "input"))
    )
    (net (code "233") (name "~{SKIP}") (class "Default")
      (node (ref "E33") (pin "1") (pinfunction "O_1") (pintype "open_collector"))
      (node (ref "E33") (pin "10") (pinfunction "O_10") (pintype "open_collector"))
      (node (ref "E33") (pin "13") (pinfunction "O_13") (pintype "open_collector"))
      (node (ref "U$1") (pin "CS1") (pinfunction "1_CS1") (pintype "bidirectional"))
    )
    (net (code "234") (name "~{STOP1}") (class "Default")
      (node (ref "E15") (pin "6") (pinfunction "~{Q}_6") (pintype "output"))
      (node (ref "STOP") (pin "3") (pinfunction "3_3") (pintype "passive"))
    )
    (net (code "235") (name "~{STOP2}") (class "Default")
      (node (ref "E19") (pin "6") (pinfunction "~{Q}_6") (pintype "output"))
      (node (ref "STOP") (pin "1") (pinfunction "1_1") (pintype "passive"))
      (node (ref "STOP2") (pin "2") (pinfunction "2_2") (pintype "passive"))
    )
    (net (code "236") (name "~{TCF}") (class "Default")
      (node (ref "E29") (pin "2") (pinfunction "I1_2") (pintype "input"))
      (node (ref "E38") (pin "11") (pinfunction "2_11") (pintype "output"))
    )
    (net (code "237") (name "~{TFLNOW}") (class "Default")
      (node (ref "E21") (pin "10") (pinfunction "PRE_10") (pintype "input"))
      (node (ref "E22") (pin "4") (pinfunction "O_4") (pintype "output"))
    )
    (net (code "238") (name "~{TFL}") (class "Default")
      (node (ref "E26") (pin "8") (pinfunction "I0_8") (pintype "input"))
      (node (ref "E38") (pin "13") (pinfunction "0_13") (pintype "output"))
    )
    (net (code "239") (name "~{TLS}") (class "Default")
      (node (ref "E29") (pin "1") (pinfunction "I0_1") (pintype "input"))
      (node (ref "E29") (pin "5") (pinfunction "I1_5") (pintype "input"))
      (node (ref "E38") (pin "4") (pinfunction "6_4") (pintype "output"))
    )
    (net (code "240") (name "~{TP3}") (class "Default")
      (node (ref "E22") (pin "2") (pinfunction "O_2") (pintype "output"))
      (node (ref "E26") (pin "11") (pinfunction "I0_11") (pintype "input"))
      (node (ref "E26") (pin "3") (pinfunction "I1_3") (pintype "input"))
      (node (ref "E26") (pin "9") (pinfunction "I1_9") (pintype "input"))
    )
    (net (code "241") (name "~{TPCNOW}") (class "Default")
      (node (ref "E32") (pin "13") (pinfunction "O_13") (pintype "open_collector"))
      (node (ref "E42") (pin "4") (pinfunction "PRE_4") (pintype "input"))
      (node (ref "E43") (pin "10") (pinfunction "I1_10") (pintype "input"))
      (node (ref "E43") (pin "11") (pinfunction "I0_11") (pintype "input"))
      (node (ref "E43") (pin "5") (pinfunction "I1_5") (pintype "input"))
      (node (ref "E43") (pin "7") (pinfunction "I1_7") (pintype "input"))
      (node (ref "E47") (pin "10") (pinfunction "I1_10") (pintype "input"))
      (node (ref "E47") (pin "11") (pinfunction "I0_11") (pintype "input"))
      (node (ref "E47") (pin "5") (pinfunction "I1_5") (pintype "input"))
      (node (ref "E47") (pin "7") (pinfunction "I1_7") (pintype "input"))
      (node (ref "R20") (pin "1") (pinfunction "1_1") (pintype "passive"))
    )
    (net (code "242") (name "~{TPC}") (class "Default")
      (node (ref "E29") (pin "4") (pinfunction "I0_4") (pintype "input"))
      (node (ref "E38") (pin "9") (pinfunction "4_9") (pintype "output"))
    )
    (net (code "243") (name "~{TSF}") (class "Default")
      (node (ref "E25") (pin "2") (pinfunction "I0_2") (pintype "input"))
      (node (ref "E38") (pin "12") (pinfunction "1_12") (pintype "output"))
    )
    (net (code "244") (name "~{TSK}") (class "Default")
      (node (ref "E25") (pin "6") (pinfunction "I1_6") (pintype "input"))
      (node (ref "E38") (pin "3") (pinfunction "5_3") (pintype "output"))
    )
    (net (code "245") (name "~{TX_BUSY}") (class "Default")
      (node (ref "E16") (pin "1") (pinfunction "I0_1") (pintype "input"))
      (node (ref "E21") (pin "12") (pinfunction "D_12") (pintype "input"))
      (node (ref "E22") (pin "10") (pinfunction "O_10") (pintype "output"))
    )
    (net (code "246") (name "~{TX_FLAG}") (class "Default")
      (node (ref "E17") (pin "5") (pinfunction "I1_5") (pintype "input"))
      (node (ref "E21") (pin "8") (pinfunction "~{Q}_8") (pintype "output"))
      (node (ref "E25") (pin "3") (pinfunction "I1_3") (pintype "input"))
    )
    (net (code "247") (name "~{XMIT_ACTIVE}") (class "Default")
      (node (ref "E15") (pin "8") (pinfunction "~{Q}_8") (pintype "output"))
      (node (ref "E6") (pin "11") (pinfunction "I_11") (pintype "input"))
    )
  )
)
